# controller.net
KiCad netlist of a schematic drawn in EAGLE
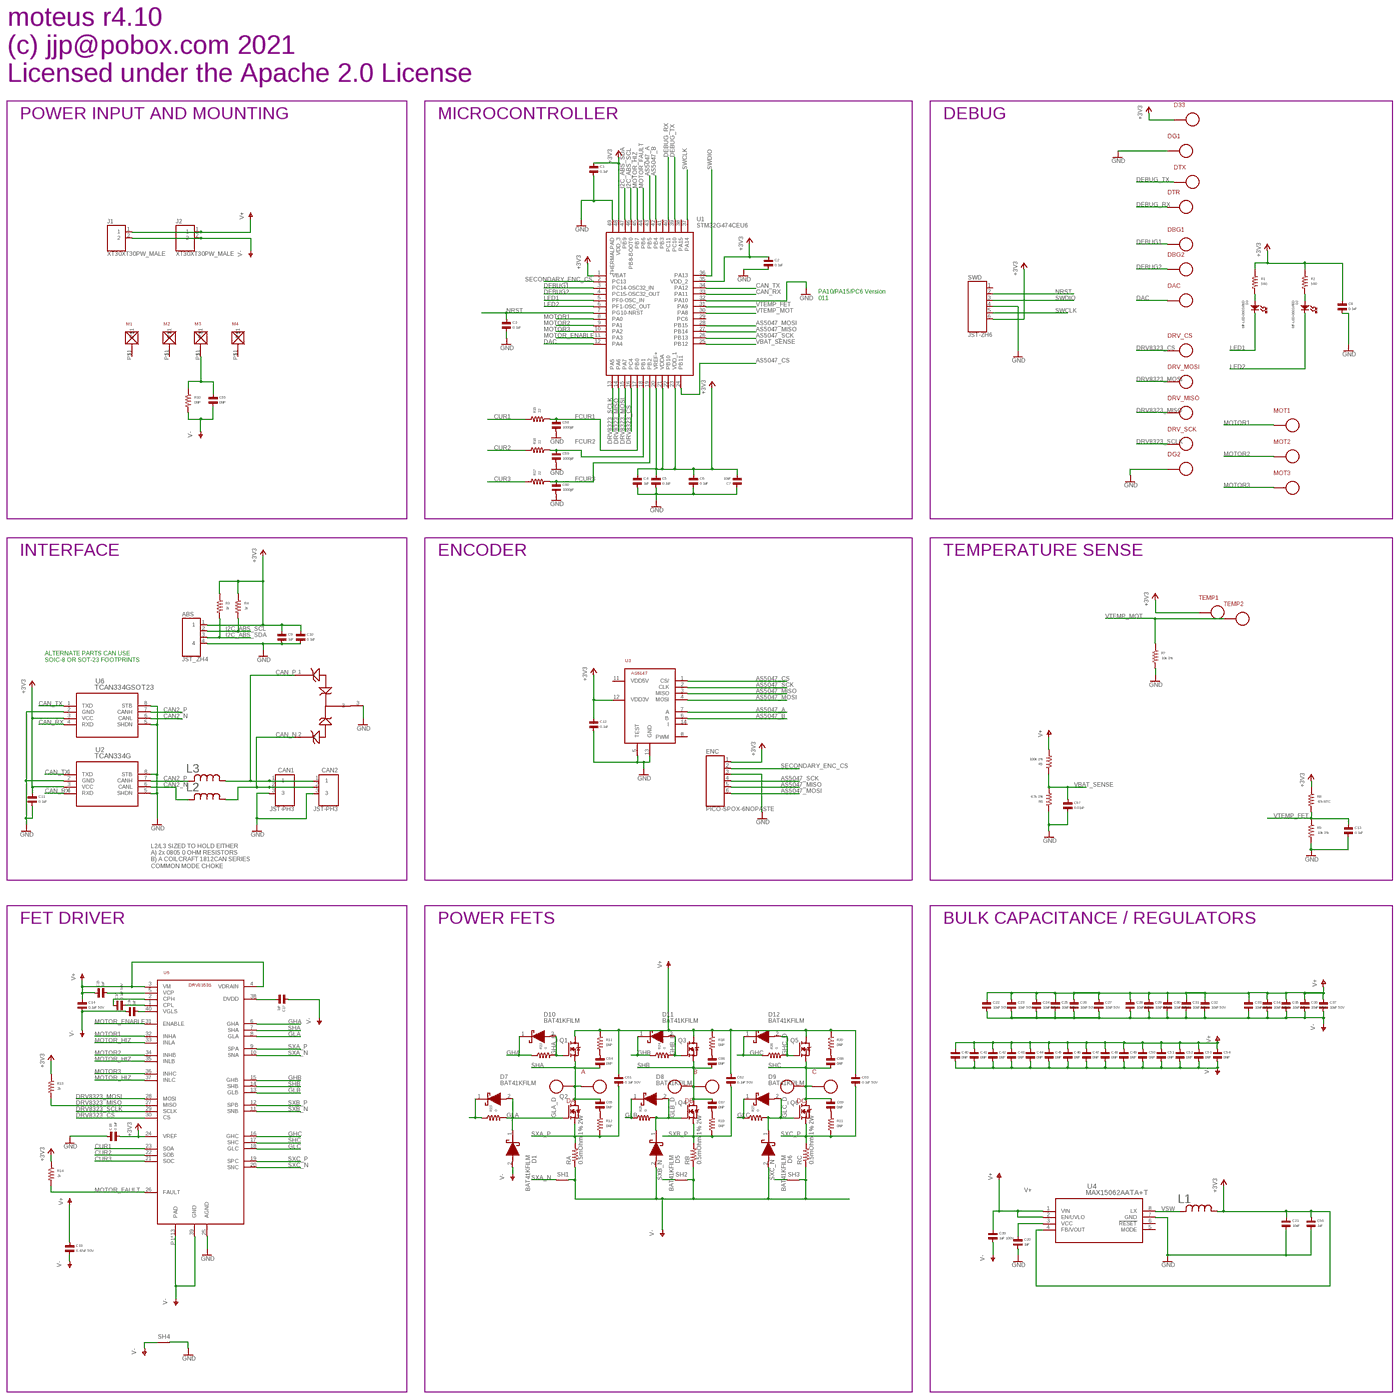
[diagram p0: schematic, sheet 1, overview]
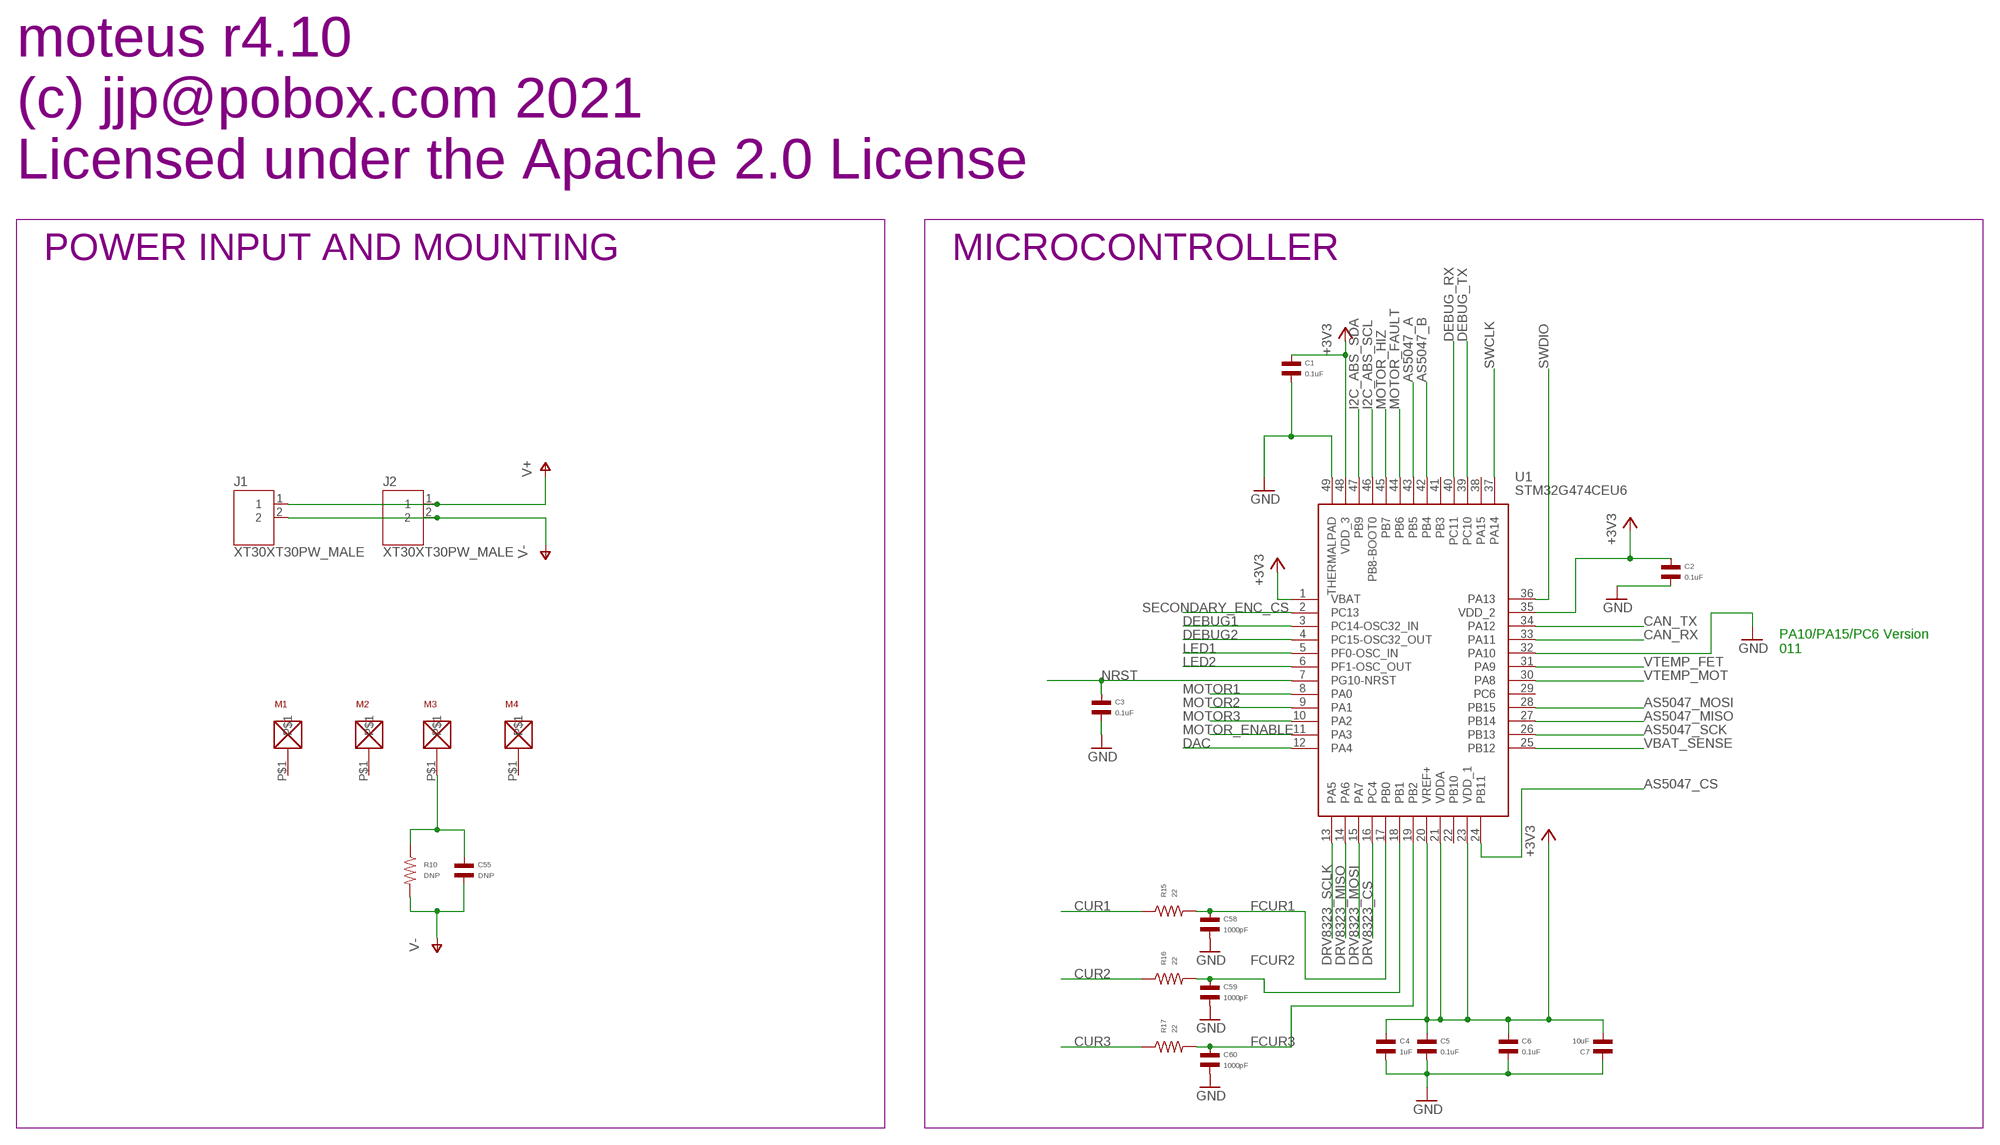
[diagram p1: schematic, sheet 1, part 1 of 4]
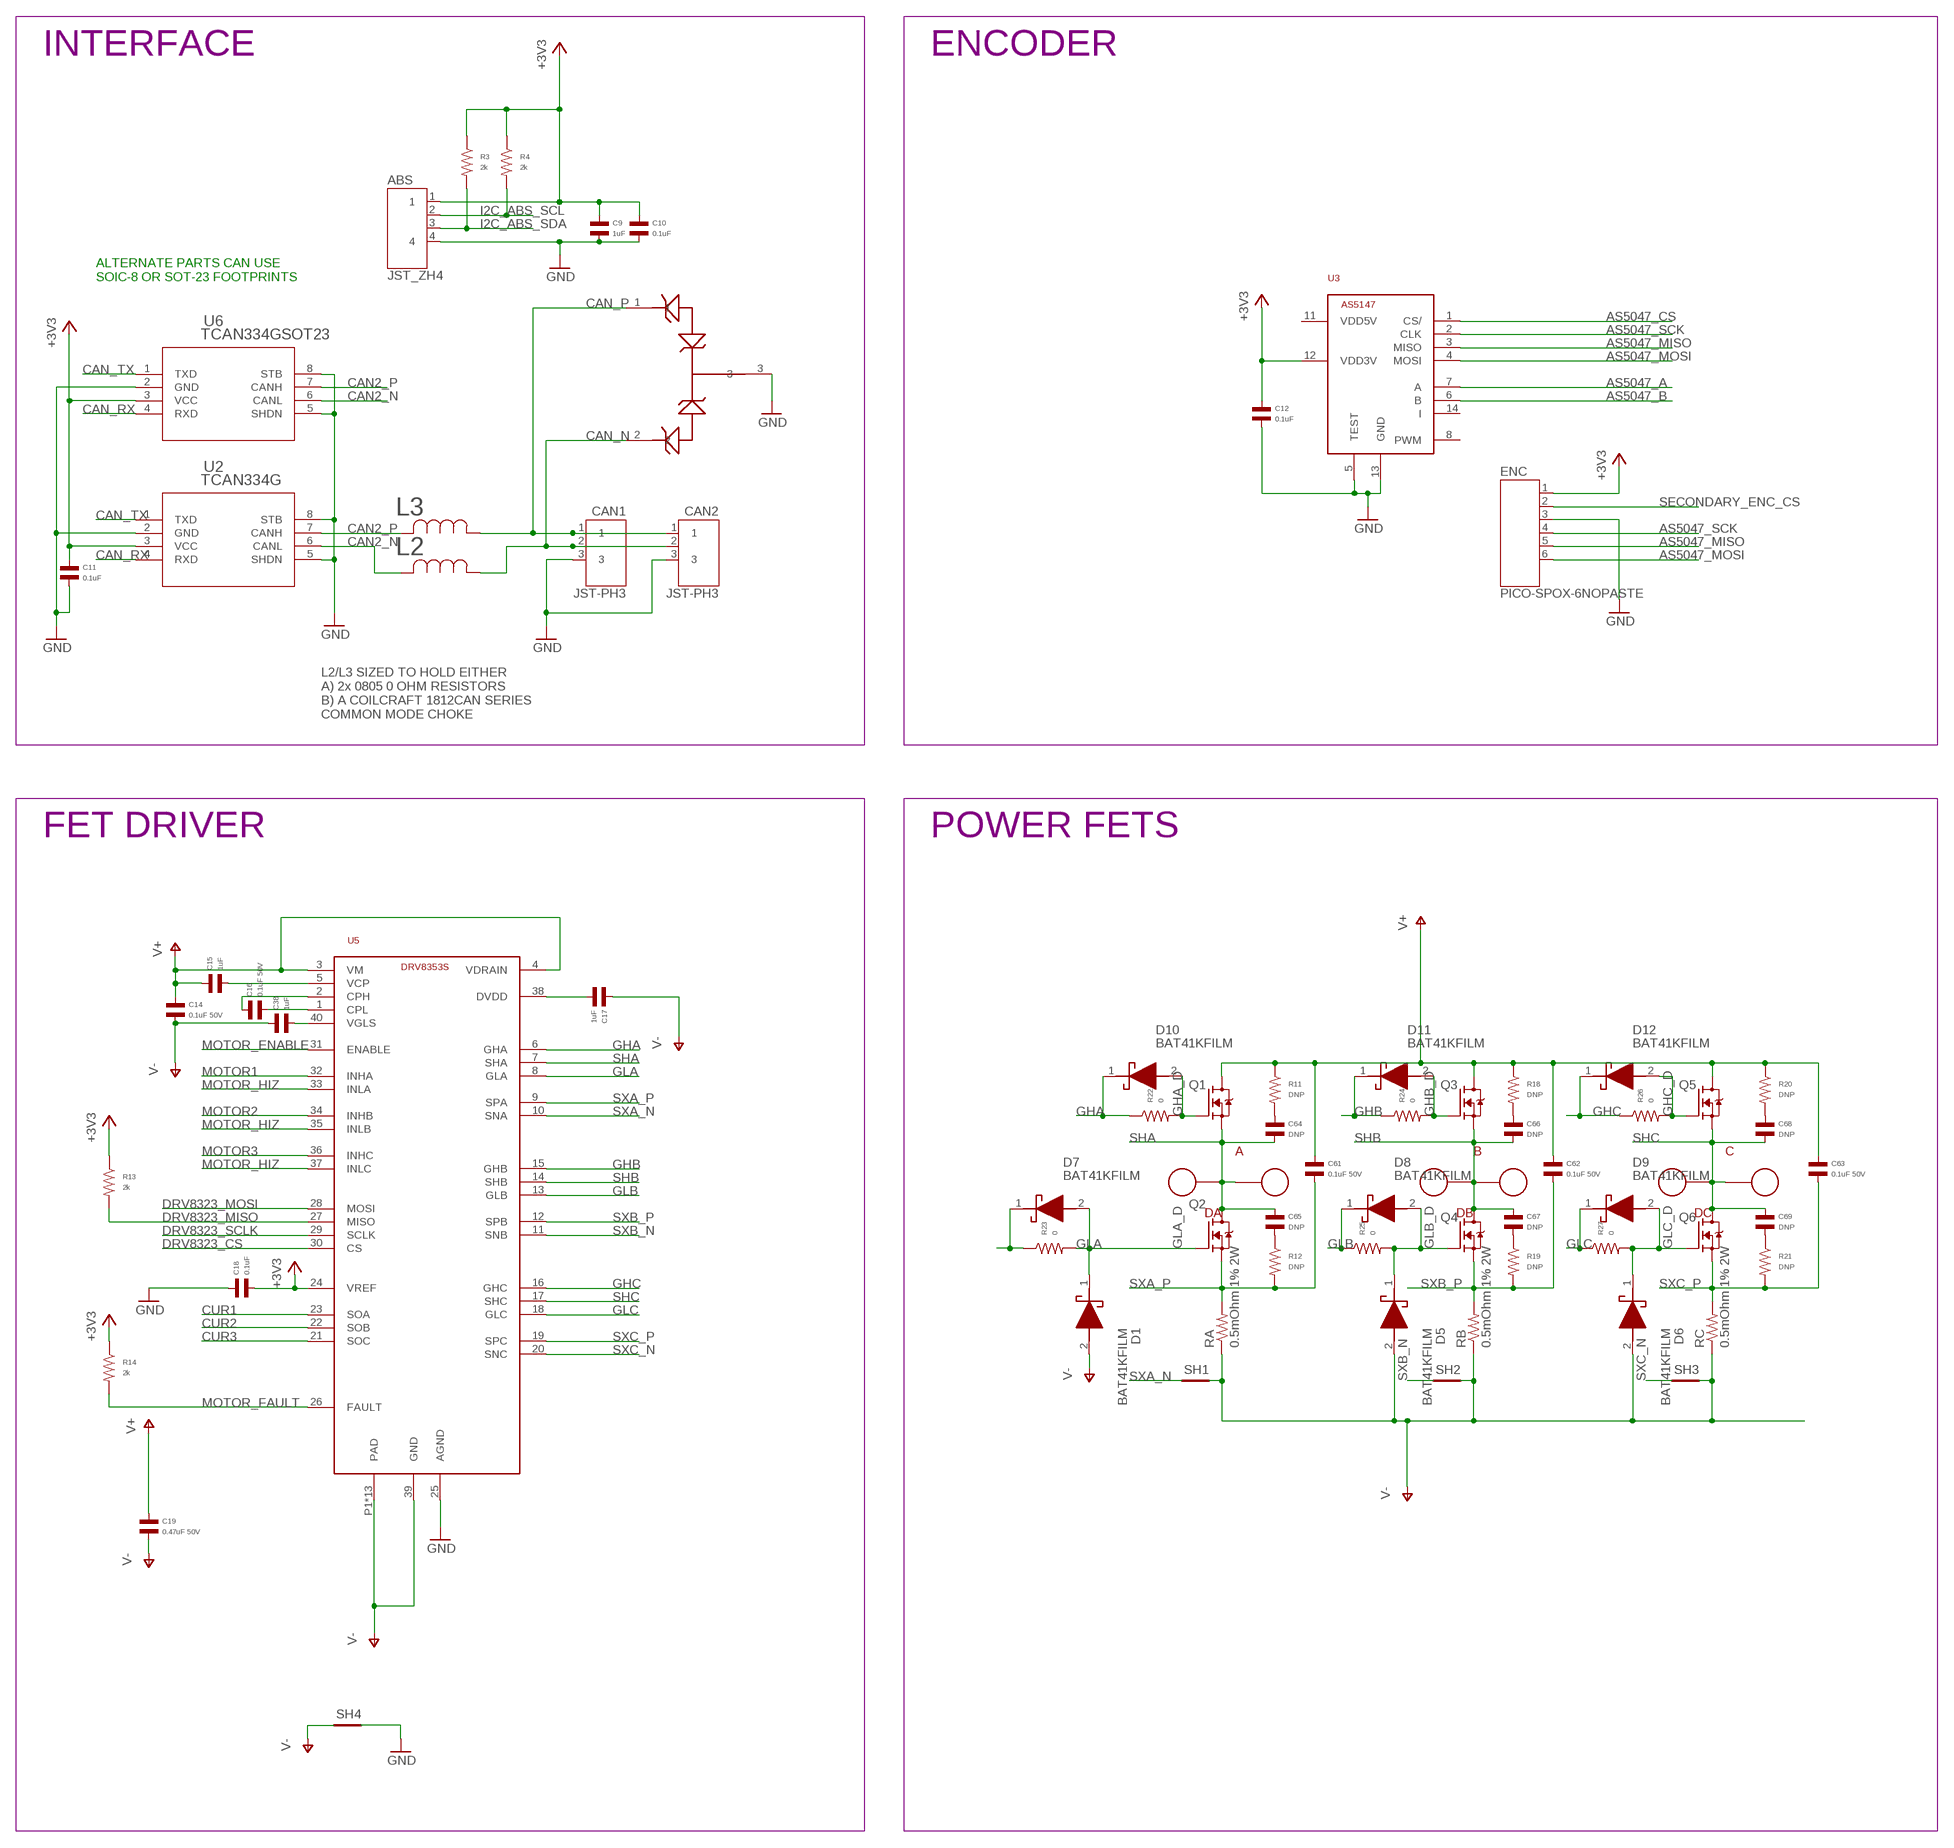
[diagram p2: schematic, sheet 1, part 2 of 4]
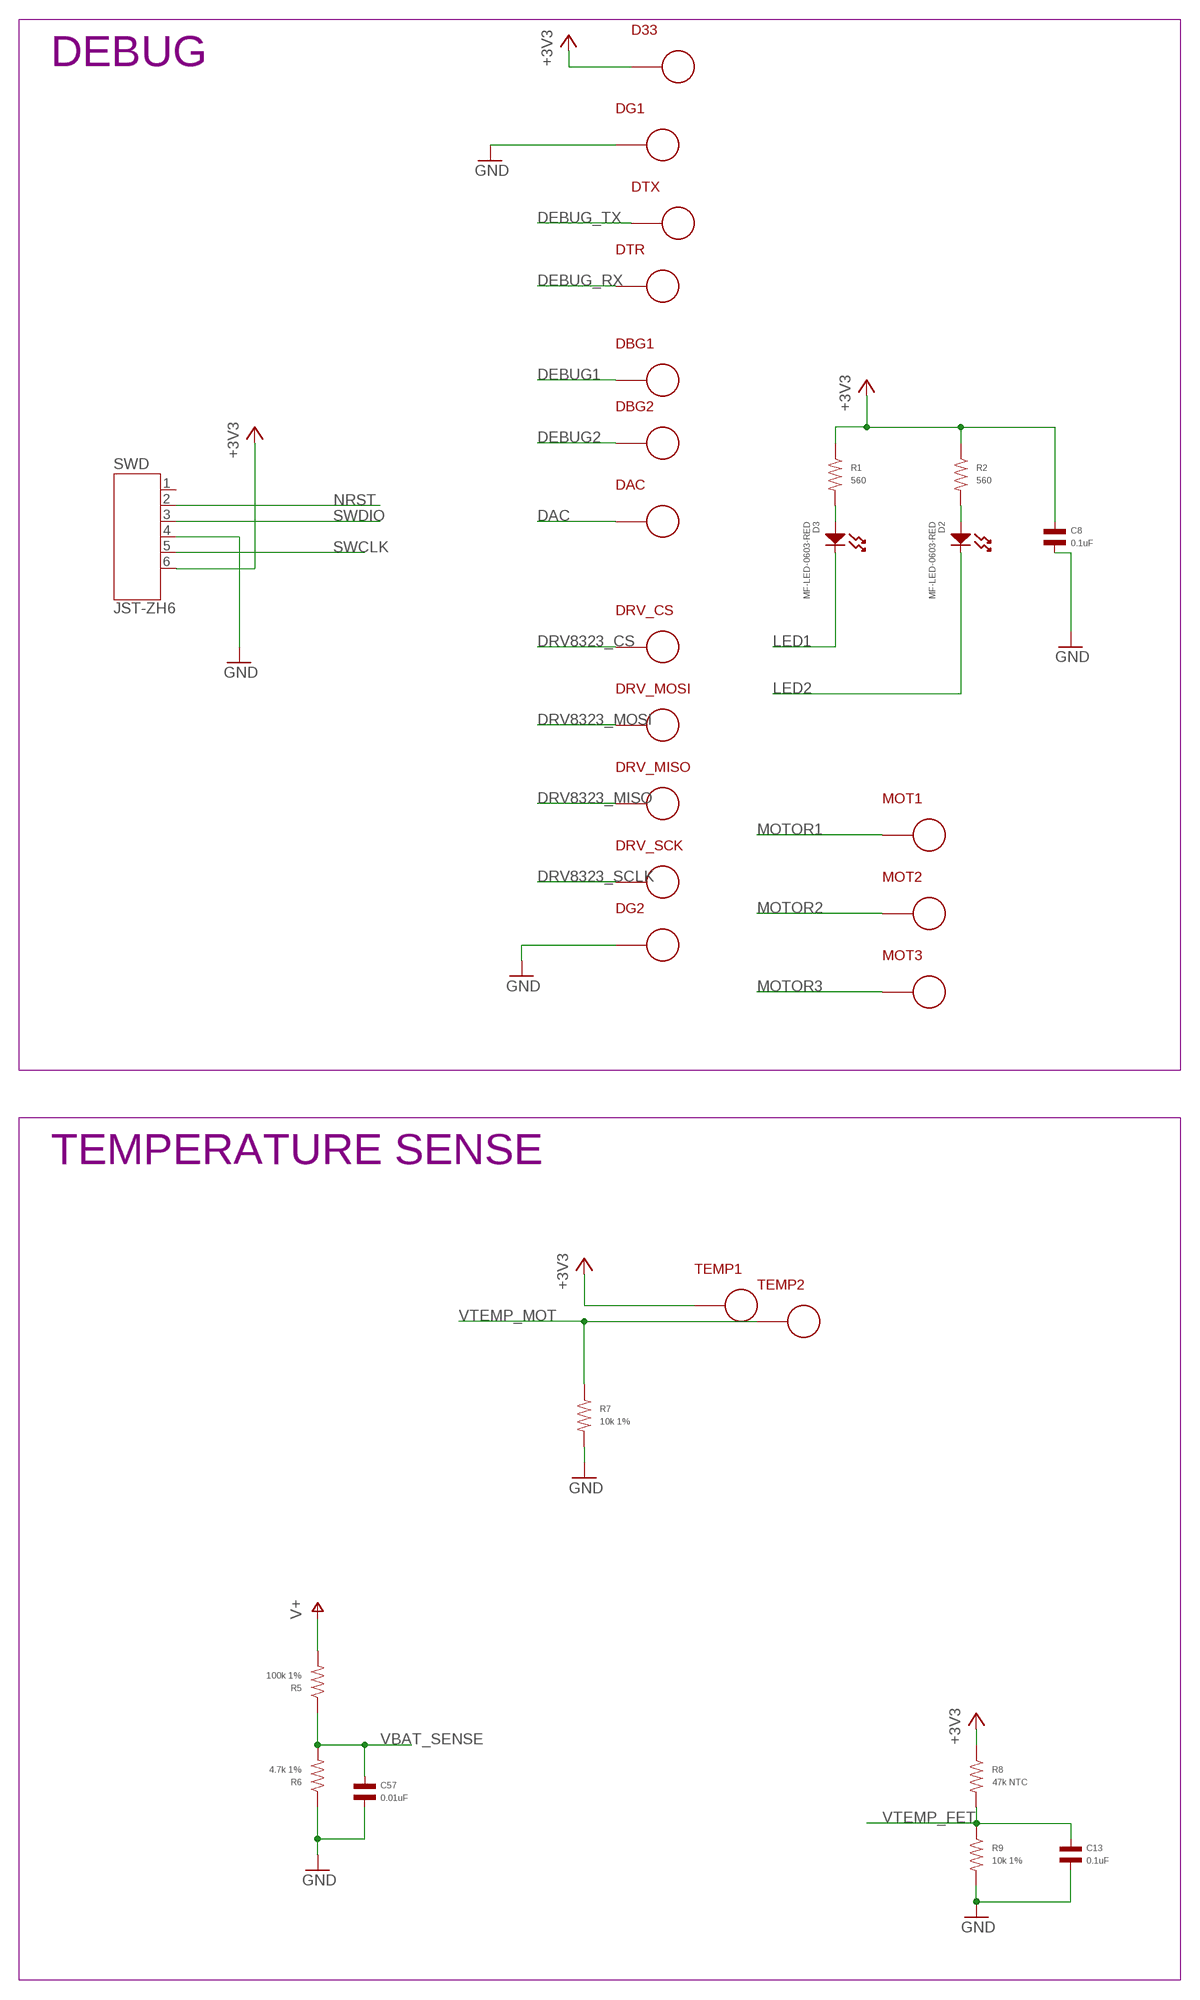
[diagram p3: schematic, sheet 1, part 3 of 4]
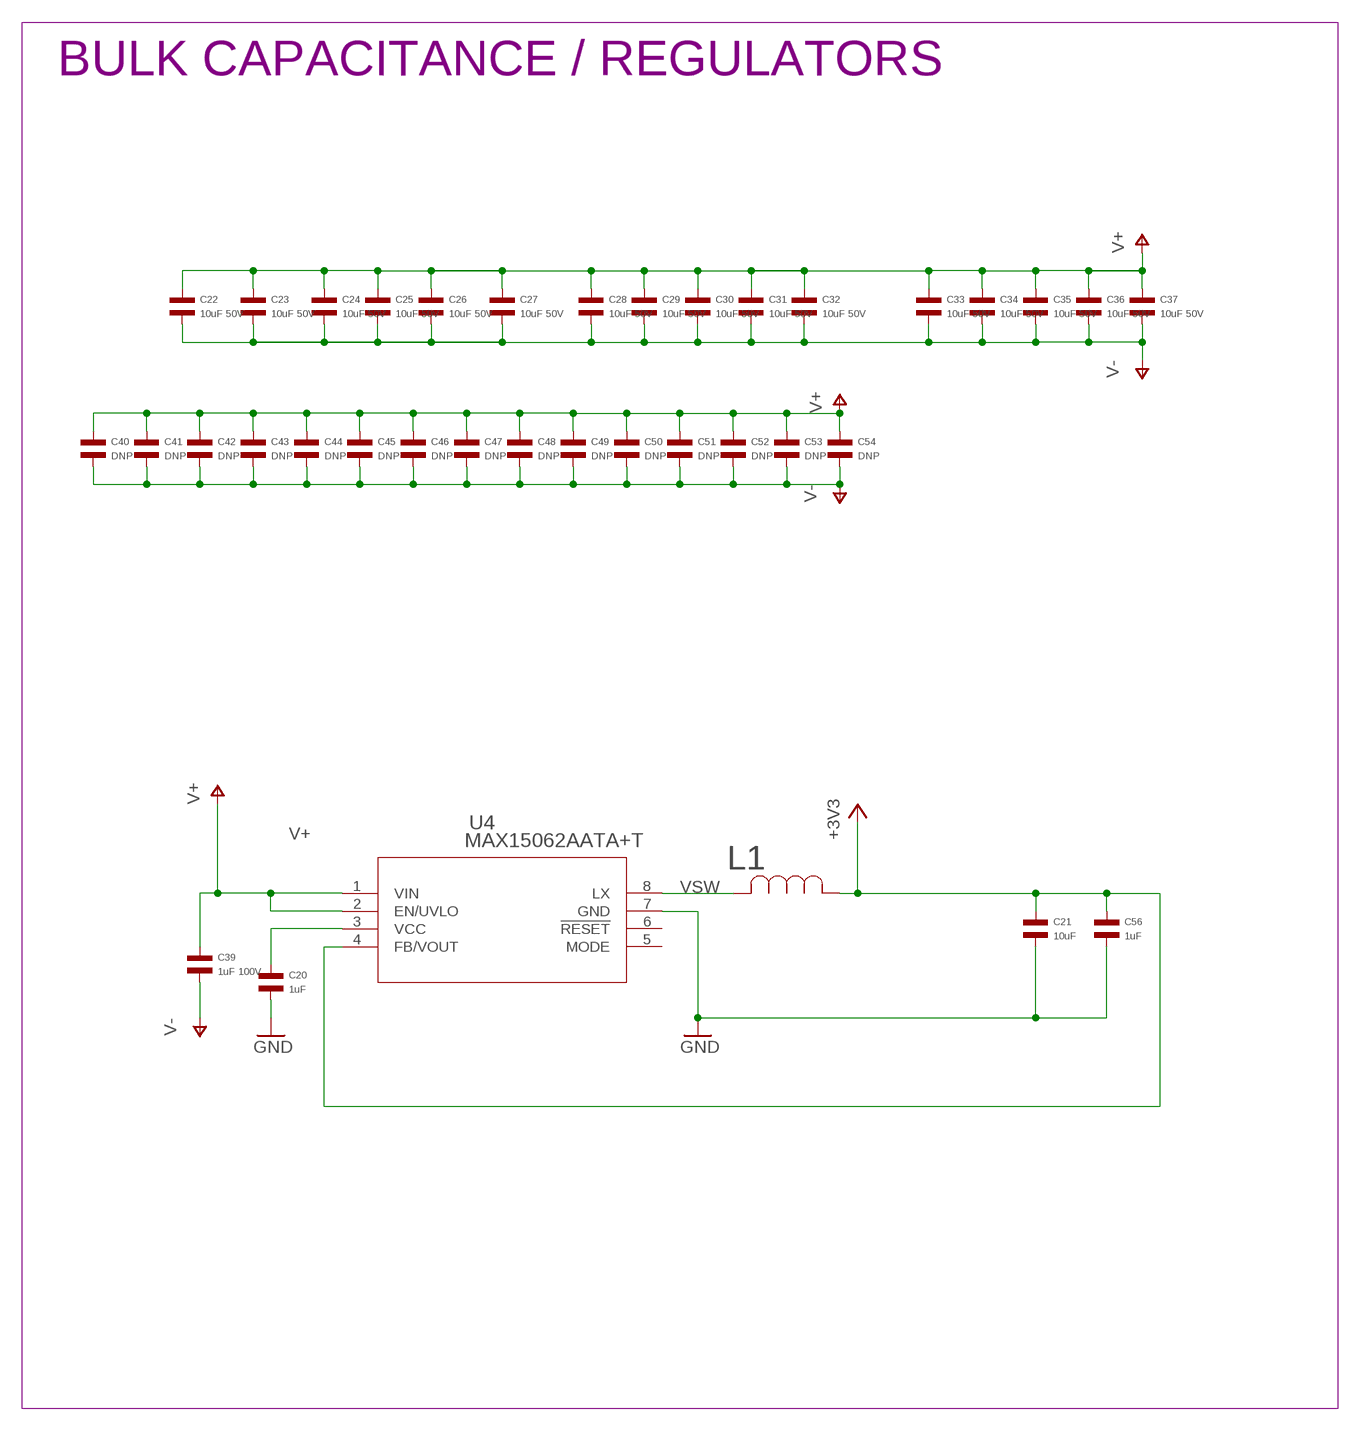
[diagram p4: schematic, sheet 1, part 4 of 4]

(export (version "E")
  (design (tool "Eeschema 10.0.6"))
  (components
    (comp (ref "A")
      (value "PAD16AWG_PAD")
      (footprint "eagle-import:16AWG_PAD")
      (libsource (lib "eagle-import") (part "PAD16AWG_PAD"))
    )
    (comp (ref "ABS")
      (value "JST_ZH4")
      (footprint "eagle-import:JST_S4B-ZR-SM4A-TF(LF)(SN)")
      (fields (field (name "MF") "JST") (field (name "MPN") "S4B-ZR-SM4A-TF(LF)(SN)"))
      (libsource (lib "eagle-import") (part "JST_ZH4"))
    )
    (comp (ref "B")
      (value "PAD16AWG_PAD")
      (footprint "eagle-import:16AWG_PAD")
      (libsource (lib "eagle-import") (part "PAD16AWG_PAD"))
    )
    (comp (ref "C")
      (value "PAD16AWG_PAD")
      (footprint "eagle-import:16AWG_PAD")
      (libsource (lib "eagle-import") (part "PAD16AWG_PAD"))
    )
    (comp (ref "C1")
      (value "0.1uF")
      (footprint "eagle-import:C0402")
      (fields (field (name "HOUSEPART") "YES") (field (name "MPN") "MF-CAP-0402-0.1uF"))
      (libsource (lib "eagle-import") (part "mfpassives_CAPACITOR_NP_0402"))
    )
    (comp (ref "C2")
      (value "0.1uF")
      (footprint "eagle-import:C0402")
      (fields (field (name "HOUSEPART") "YES") (field (name "MPN") "MF-CAP-0402-0.1uF"))
      (libsource (lib "eagle-import") (part "mfpassives_CAPACITOR_NP_0402"))
    )
    (comp (ref "C3")
      (value "0.1uF")
      (footprint "eagle-import:C0402")
      (fields (field (name "HOUSEPART") "YES") (field (name "MPN") "MF-CAP-0402-0.1uF"))
      (libsource (lib "eagle-import") (part "mfpassives_CAPACITOR_NP_0402"))
    )
    (comp (ref "C4")
      (value "1uF")
      (footprint "eagle-import:C0402")
      (fields (field (name "HOUSEPART") "YES") (field (name "MPN") "MF-CAP-0402-1uF"))
      (libsource (lib "eagle-import") (part "mfpassives_CAPACITOR_NP_0402"))
    )
    (comp (ref "C5")
      (value "0.1uF")
      (footprint "eagle-import:C0402")
      (fields (field (name "HOUSEPART") "YES") (field (name "MPN") "MF-CAP-0402-0.1uF"))
      (libsource (lib "eagle-import") (part "mfpassives_CAPACITOR_NP_0402"))
    )
    (comp (ref "C6")
      (value "0.1uF")
      (footprint "eagle-import:C0402")
      (fields (field (name "HOUSEPART") "YES") (field (name "MPN") "MF-CAP-0402-0.1uF"))
      (libsource (lib "eagle-import") (part "mfpassives_CAPACITOR_NP_0402"))
    )
    (comp (ref "C7")
      (value "10uF")
      (footprint "eagle-import:C1206")
      (fields (field (name "HOUSEPART") "YES") (field (name "MPN") "MF-CAP-1206-10uF"))
      (libsource (lib "eagle-import") (part "mfpassives_CAPACITOR_NP_1206"))
    )
    (comp (ref "C8")
      (value "0.1uF")
      (footprint "eagle-import:C0402")
      (fields (field (name "HOUSEPART") "YES") (field (name "MPN") "MF-CAP-0402-0.1uF"))
      (libsource (lib "eagle-import") (part "mfpassives_CAPACITOR_NP_0402"))
    )
    (comp (ref "C9")
      (value "1uF")
      (footprint "eagle-import:C0402")
      (fields (field (name "HOUSEPART") "YES") (field (name "MPN") "MF-CAP-0402-1uF"))
      (libsource (lib "eagle-import") (part "mfpassives_CAPACITOR_NP_0402"))
    )
    (comp (ref "C10")
      (value "0.1uF")
      (footprint "eagle-import:C0402")
      (fields (field (name "HOUSEPART") "YES") (field (name "MPN") "MF-CAP-0402-0.1uF"))
      (libsource (lib "eagle-import") (part "mfpassives_CAPACITOR_NP_0402"))
    )
    (comp (ref "C11")
      (value "0.1uF")
      (footprint "eagle-import:C0402_NOBORDER")
      (fields (field (name "HOUSEPART") "YES") (field (name "MPN") "MF-CAP-0402-0.1uF"))
      (libsource (lib "eagle-import") (part "CAPACITOR_NP_0402_NOBORDER"))
    )
    (comp (ref "C12")
      (value "0.1uF")
      (footprint "eagle-import:C0402")
      (fields (field (name "HOUSEPART") "YES") (field (name "MPN") "MF-CAP-0402-0.1uF"))
      (libsource (lib "eagle-import") (part "mfpassives_CAPACITOR_NP_0402"))
    )
    (comp (ref "C13")
      (value "0.1uF")
      (footprint "eagle-import:C0402")
      (fields (field (name "HOUSEPART") "YES") (field (name "MPN") "MF-CAP-0402-0.1uF"))
      (libsource (lib "eagle-import") (part "mfpassives_CAPACITOR_NP_0402"))
    )
    (comp (ref "C14")
      (value "0.1uF 50V")
      (footprint "eagle-import:C0402")
      (fields (field (name "MF") "TDK") (field (name "MPN") "CGA2B3X7R1H104K050BB"))
      (libsource (lib "eagle-import") (part "mfpassives_CAPACITOR_NP_0402"))
    )
    (comp (ref "C15")
      (value "1uF")
      (footprint "eagle-import:C0402")
      (fields (field (name "HOUSEPART") "YES") (field (name "MPN") "MF-CAP-0402-1uF"))
      (libsource (lib "eagle-import") (part "mfpassives_CAPACITOR_NP_0402"))
    )
    (comp (ref "C16")
      (value "0.1uF 50V")
      (footprint "eagle-import:C0402")
      (fields (field (name "MF") "TDK") (field (name "MPN") "CGA2B3X7R1H104K050BB"))
      (libsource (lib "eagle-import") (part "mfpassives_CAPACITOR_NP_0402"))
    )
    (comp (ref "C17")
      (value "1uF")
      (footprint "eagle-import:C0402")
      (fields (field (name "HOUSEPART") "YES") (field (name "MPN") "MF-CAP-0402-1uF"))
      (libsource (lib "eagle-import") (part "mfpassives_CAPACITOR_NP_0402"))
    )
    (comp (ref "C18")
      (value "0.1uF")
      (footprint "eagle-import:C0402")
      (fields (field (name "HOUSEPART") "YES") (field (name "MPN") "MF-CAP-0402-0.1uF"))
      (libsource (lib "eagle-import") (part "mfpassives_CAPACITOR_NP_0402"))
    )
    (comp (ref "C19")
      (value "0.47uF 50V")
      (footprint "eagle-import:C0402")
      (fields (field (name "MF") "Murata") (field (name "MPN") "GRM155R61H474KE11D"))
      (libsource (lib "eagle-import") (part "mfpassives_CAPACITOR_NP_0402"))
    )
    (comp (ref "C20")
      (value "1uF")
      (footprint "eagle-import:C0603")
      (fields (field (name "HOUSEPART") "1") (field (name "MPN") "MF-CAP-0603-1uF"))
      (libsource (lib "eagle-import") (part "mfpassives_CAPACITOR_NP_0603"))
    )
    (comp (ref "C21")
      (value "10uF")
      (footprint "eagle-import:C1206")
      (fields (field (name "HOUSEPART") "1") (field (name "MPN") "MF-CAP-1206-10uF"))
      (libsource (lib "eagle-import") (part "mfpassives_CAPACITOR_NP_1206"))
    )
    (comp (ref "C22")
      (value "10uF 50V")
      (footprint "eagle-import:C1206")
      (fields (field (name "MF") "TDK") (field (name "MPN") "C3216X7R1H106K160AE"))
      (libsource (lib "eagle-import") (part "mfpassives_CAPACITOR_NP_1206"))
    )
    (comp (ref "C23")
      (value "10uF 50V")
      (footprint "eagle-import:C1206")
      (fields (field (name "MF") "TDK") (field (name "MPN") "C3216X7R1H106K160AE"))
      (libsource (lib "eagle-import") (part "mfpassives_CAPACITOR_NP_1206"))
    )
    (comp (ref "C24")
      (value "10uF 50V")
      (footprint "eagle-import:C1206")
      (fields (field (name "MF") "TDK") (field (name "MPN") "C3216X7R1H106K160AE"))
      (libsource (lib "eagle-import") (part "mfpassives_CAPACITOR_NP_1206"))
    )
    (comp (ref "C25")
      (value "10uF 50V")
      (footprint "eagle-import:C1206")
      (fields (field (name "MF") "TDK") (field (name "MPN") "C3216X7R1H106K160AE"))
      (libsource (lib "eagle-import") (part "mfpassives_CAPACITOR_NP_1206"))
    )
    (comp (ref "C26")
      (value "10uF 50V")
      (footprint "eagle-import:C1206")
      (fields (field (name "MF") "TDK") (field (name "MPN") "C3216X7R1H106K160AE"))
      (libsource (lib "eagle-import") (part "mfpassives_CAPACITOR_NP_1206"))
    )
    (comp (ref "C27")
      (value "10uF 50V")
      (footprint "eagle-import:C1206")
      (fields (field (name "MF") "TDK") (field (name "MPN") "C3216X7R1H106K160AE"))
      (libsource (lib "eagle-import") (part "mfpassives_CAPACITOR_NP_1206"))
    )
    (comp (ref "C28")
      (value "10uF 50V")
      (footprint "eagle-import:C1206")
      (fields (field (name "MF") "TDK") (field (name "MPN") "C3216X7R1H106K160AE"))
      (libsource (lib "eagle-import") (part "mfpassives_CAPACITOR_NP_1206"))
    )
    (comp (ref "C29")
      (value "10uF 50V")
      (footprint "eagle-import:C1206")
      (fields (field (name "MF") "TDK") (field (name "MPN") "C3216X7R1H106K160AE"))
      (libsource (lib "eagle-import") (part "mfpassives_CAPACITOR_NP_1206"))
    )
    (comp (ref "C30")
      (value "10uF 50V")
      (footprint "eagle-import:C1206")
      (fields (field (name "MF") "TDK") (field (name "MPN") "C3216X7R1H106K160AE"))
      (libsource (lib "eagle-import") (part "mfpassives_CAPACITOR_NP_1206"))
    )
    (comp (ref "C31")
      (value "10uF 50V")
      (footprint "eagle-import:C1206")
      (fields (field (name "MF") "TDK") (field (name "MPN") "C3216X7R1H106K160AE"))
      (libsource (lib "eagle-import") (part "mfpassives_CAPACITOR_NP_1206"))
    )
    (comp (ref "C32")
      (value "10uF 50V")
      (footprint "eagle-import:C1206")
      (fields (field (name "MF") "TDK") (field (name "MPN") "C3216X7R1H106K160AE"))
      (libsource (lib "eagle-import") (part "mfpassives_CAPACITOR_NP_1206"))
    )
    (comp (ref "C33")
      (value "10uF 50V")
      (footprint "eagle-import:C1206")
      (fields (field (name "MF") "TDK") (field (name "MPN") "C3216X7R1H106K160AE"))
      (libsource (lib "eagle-import") (part "mfpassives_CAPACITOR_NP_1206"))
    )
    (comp (ref "C34")
      (value "10uF 50V")
      (footprint "eagle-import:C1206")
      (fields (field (name "MF") "TDK") (field (name "MPN") "C3216X7R1H106K160AE"))
      (libsource (lib "eagle-import") (part "mfpassives_CAPACITOR_NP_1206"))
    )
    (comp (ref "C35")
      (value "10uF 50V")
      (footprint "eagle-import:C1206_NOBORDER")
      (fields (field (name "MF") "TDK") (field (name "MPN") "C3216X7R1H106K160AE"))
      (libsource (lib "eagle-import") (part "CAPACITOR_NP_1206_NOBORDER"))
    )
    (comp (ref "C36")
      (value "10uF 50V")
      (footprint "eagle-import:C1206")
      (fields (field (name "MF") "TDK") (field (name "MPN") "C3216X7R1H106K160AE"))
      (libsource (lib "eagle-import") (part "mfpassives_CAPACITOR_NP_1206"))
    )
    (comp (ref "C37")
      (value "10uF 50V")
      (footprint "eagle-import:C1206")
      (fields (field (name "MF") "TDK") (field (name "MPN") "C3216X7R1H106K160AE"))
      (libsource (lib "eagle-import") (part "mfpassives_CAPACITOR_NP_1206"))
    )
    (comp (ref "C38")
      (value "1uF")
      (footprint "eagle-import:C0603")
      (fields
        (field (name "HOUSEPART") "YES")
        (field (name "MF") "TDK")
        (field (name "MPN") "C1608X7R1E105K080AE")
      )
      (libsource (lib "eagle-import") (part "mfpassives_CAPACITOR_NP_0603"))
    )
    (comp (ref "C39")
      (value "1uF 100V")
      (footprint "eagle-import:C0805")
      (fields (field (name "MF") "MURATA") (field (name "MPN") "GCM21BC72A105KE36L"))
      (libsource (lib "eagle-import") (part "mfpassives_CAPACITOR_NP_0805"))
    )
    (comp (ref "C40")
      (value "DNP")
      (footprint "eagle-import:C1206_NOCREAM")
      (libsource (lib "eagle-import") (part "CAPACITOR_NP_1206_NOCREAM"))
    )
    (comp (ref "C41")
      (value "DNP")
      (footprint "eagle-import:C1206_NOCREAM")
      (libsource (lib "eagle-import") (part "CAPACITOR_NP_1206_NOCREAM"))
    )
    (comp (ref "C42")
      (value "DNP")
      (footprint "eagle-import:C1206_NOCREAM")
      (libsource (lib "eagle-import") (part "CAPACITOR_NP_1206_NOCREAM"))
    )
    (comp (ref "C43")
      (value "DNP")
      (footprint "eagle-import:C1206_NOCREAM")
      (libsource (lib "eagle-import") (part "CAPACITOR_NP_1206_NOCREAM"))
    )
    (comp (ref "C44")
      (value "DNP")
      (footprint "eagle-import:C1206_NOCREAM")
      (libsource (lib "eagle-import") (part "CAPACITOR_NP_1206_NOCREAM"))
    )
    (comp (ref "C45")
      (value "DNP")
      (footprint "eagle-import:C1206_NOCREAM")
      (libsource (lib "eagle-import") (part "CAPACITOR_NP_1206_NOCREAM"))
    )
    (comp (ref "C46")
      (value "DNP")
      (footprint "eagle-import:C1206_NOCREAM")
      (libsource (lib "eagle-import") (part "CAPACITOR_NP_1206_NOCREAM"))
    )
    (comp (ref "C47")
      (value "DNP")
      (footprint "eagle-import:C1206_NOCREAM")
      (libsource (lib "eagle-import") (part "CAPACITOR_NP_1206_NOCREAM"))
    )
    (comp (ref "C48")
      (value "DNP")
      (footprint "eagle-import:C1206_NOCREAM")
      (libsource (lib "eagle-import") (part "CAPACITOR_NP_1206_NOCREAM"))
    )
    (comp (ref "C49")
      (value "DNP")
      (footprint "eagle-import:C1206_NOCREAM")
      (libsource (lib "eagle-import") (part "CAPACITOR_NP_1206_NOCREAM"))
    )
    (comp (ref "C50")
      (value "DNP")
      (footprint "eagle-import:C1206_NOCREAM")
      (libsource (lib "eagle-import") (part "CAPACITOR_NP_1206_NOCREAM"))
    )
    (comp (ref "C51")
      (value "DNP")
      (footprint "eagle-import:C1206_NOCREAM")
      (libsource (lib "eagle-import") (part "CAPACITOR_NP_1206_NOCREAM"))
    )
    (comp (ref "C52")
      (value "DNP")
      (footprint "eagle-import:C1206_NOCREAM")
      (libsource (lib "eagle-import") (part "CAPACITOR_NP_1206_NOCREAM"))
    )
    (comp (ref "C53")
      (value "DNP")
      (footprint "eagle-import:C1206_NOCREAM")
      (libsource (lib "eagle-import") (part "CAPACITOR_NP_1206_NOCREAM"))
    )
    (comp (ref "C54")
      (value "DNP")
      (footprint "eagle-import:C1206_NOCREAM")
      (libsource (lib "eagle-import") (part "CAPACITOR_NP_1206_NOCREAM"))
    )
    (comp (ref "C55")
      (value "DNP")
      (footprint "eagle-import:C0402")
      (fields (field (name "POPULATE") "0"))
      (libsource (lib "eagle-import") (part "mfpassives_CAPACITOR_NP_0402"))
    )
    (comp (ref "C56")
      (value "1uF")
      (footprint "eagle-import:C0402")
      (fields (field (name "HOUSEPART") "YES") (field (name "MPN") "MF-CAP-0402-1uF"))
      (libsource (lib "eagle-import") (part "mfpassives_CAPACITOR_NP_0402"))
    )
    (comp (ref "C57")
      (value "0.01uF")
      (footprint "eagle-import:C0402")
      (fields (field (name "HOUSEPART") "YES") (field (name "MPN") "MF-CAP-0402-0.01uF"))
      (libsource (lib "eagle-import") (part "mfpassives_CAPACITOR_NP_0402"))
    )
    (comp (ref "C58")
      (value "1000pF")
      (footprint "eagle-import:C0402_NOBORDER")
      (fields (field (name "HOUSEPART") "1") (field (name "MPN") "MF-CAP-0402-1nF"))
      (libsource (lib "eagle-import") (part "CAPACITOR_NP_0402_NOBORDER"))
    )
    (comp (ref "C59")
      (value "1000pF")
      (footprint "eagle-import:C0402_NOBORDER")
      (fields (field (name "HOUSEPART") "1") (field (name "MPN") "MF-CAP-0402-1nF"))
      (libsource (lib "eagle-import") (part "CAPACITOR_NP_0402_NOBORDER"))
    )
    (comp (ref "C60")
      (value "1000pF")
      (footprint "eagle-import:C0402_NOBORDER")
      (fields (field (name "HOUSEPART") "1") (field (name "MPN") "MF-CAP-0402-1nF"))
      (libsource (lib "eagle-import") (part "CAPACITOR_NP_0402_NOBORDER"))
    )
    (comp (ref "C61")
      (value "0.1uF 50V")
      (footprint "eagle-import:C1206")
      (fields (field (name "MF") "KYOCERA AVX") (field (name "MPN") "12065C104KAZ2A"))
      (libsource (lib "eagle-import") (part "mfpassives_CAPACITOR_NP_1206"))
    )
    (comp (ref "C62")
      (value "0.1uF 50V")
      (footprint "eagle-import:C0603_NOBORDER")
      (fields (field (name "MF") "KYOCERA AVX") (field (name "MPN") "06035C104KAZ2A"))
      (libsource (lib "eagle-import") (part "CAPACITOR_NP_0603_NOBORDER"))
    )
    (comp (ref "C63")
      (value "0.1uF 50V")
      (footprint "eagle-import:C1206")
      (fields (field (name "MF") "KYOCERA AVX") (field (name "MPN") "12065C104KAZ2A"))
      (libsource (lib "eagle-import") (part "mfpassives_CAPACITOR_NP_1206"))
    )
    (comp (ref "C64")
      (value "DNP")
      (footprint "eagle-import:C0603")
      (fields (field (name "POPULATE") "0"))
      (libsource (lib "eagle-import") (part "mfpassives_CAPACITOR_NP_0603"))
    )
    (comp (ref "C65")
      (value "DNP")
      (footprint "eagle-import:C0603")
      (fields (field (name "POPULATE") "0"))
      (libsource (lib "eagle-import") (part "mfpassives_CAPACITOR_NP_0603"))
    )
    (comp (ref "C66")
      (value "DNP")
      (footprint "eagle-import:C0603")
      (fields (field (name "POPULATE") "0"))
      (libsource (lib "eagle-import") (part "mfpassives_CAPACITOR_NP_0603"))
    )
    (comp (ref "C67")
      (value "DNP")
      (footprint "eagle-import:C0603")
      (fields (field (name "POPULATE") "0"))
      (libsource (lib "eagle-import") (part "mfpassives_CAPACITOR_NP_0603"))
    )
    (comp (ref "C68")
      (value "DNP")
      (footprint "eagle-import:C0603")
      (fields (field (name "POPULATE") "0"))
      (libsource (lib "eagle-import") (part "mfpassives_CAPACITOR_NP_0603"))
    )
    (comp (ref "C69")
      (value "DNP")
      (footprint "eagle-import:C0603")
      (fields (field (name "POPULATE") "0"))
      (libsource (lib "eagle-import") (part "mfpassives_CAPACITOR_NP_0603"))
    )
    (comp (ref "CAN1")
      (value "JST-PH3")
      (footprint "eagle-import:JST_S3B-PH-SM4-TB(LF)(SN)")
      (fields (field (name "MF") "JST") (field (name "MPN") "S3B-PH-SM4-TB(LF)(SN)"))
      (libsource (lib "eagle-import") (part "JST-PH3"))
    )
    (comp (ref "CAN2")
      (value "JST-PH3")
      (footprint "eagle-import:JST_S3B-PH-SM4-TB(LF)(SN)")
      (fields (field (name "MF") "JST") (field (name "MPN") "S3B-PH-SM4-TB(LF)(SN)"))
      (libsource (lib "eagle-import") (part "JST-PH3"))
    )
    (comp (ref "D1")
      (value "BAT41KFILM")
      (footprint "eagle-import:SODFL1608X70N")
      (fields (field (name "MOUSER_PART_NUMBER") "511-BAT41KFILM") (field (name "MF") "ST"))
      (libsource (lib "eagle-import") (part "BAT41KFILM"))
    )
    (comp (ref "D2")
      (value "MF-LED-0603-RED")
      (footprint "eagle-import:LED0603")
      (fields (field (name "HOUSEPART") "YES") (field (name "MPN") "MF-LED-0603-GREEN"))
      (libsource (lib "eagle-import") (part "LED_SINGLE-0603-RED"))
    )
    (comp (ref "D3")
      (value "MF-LED-0603-RED")
      (footprint "eagle-import:LED0603")
      (fields (field (name "HOUSEPART") "YES"))
      (libsource (lib "eagle-import") (part "LED_SINGLE-0603-RED"))
    )
    (comp (ref "D4")
      (value "DUAL_TVS")
      (footprint "eagle-import:SOT23-3")
      (fields (field (name "MPN") "CDSOT23-0502B"))
      (libsource (lib "eagle-import") (part "DUAL_TVS"))
    )
    (comp (ref "D5")
      (value "BAT41KFILM")
      (footprint "eagle-import:SODFL1608X70N")
      (fields (field (name "MOUSER_PART_NUMBER") "511-BAT41KFILM") (field (name "MF") "ST"))
      (libsource (lib "eagle-import") (part "BAT41KFILM"))
    )
    (comp (ref "D6")
      (value "BAT41KFILM")
      (footprint "eagle-import:SODFL1608X70N")
      (fields (field (name "MOUSER_PART_NUMBER") "511-BAT41KFILM") (field (name "MF") "ST"))
      (libsource (lib "eagle-import") (part "BAT41KFILM"))
    )
    (comp (ref "D7")
      (value "BAT41KFILM")
      (footprint "eagle-import:SODFL1608X70N")
      (fields (field (name "MOUSER_PART_NUMBER") "511-BAT41KFILM") (field (name "MF") "ST"))
      (libsource (lib "eagle-import") (part "BAT41KFILM"))
    )
    (comp (ref "D8")
      (value "BAT41KFILM")
      (footprint "eagle-import:SODFL1608X70N")
      (fields (field (name "MOUSER_PART_NUMBER") "511-BAT41KFILM") (field (name "MF") "ST"))
      (libsource (lib "eagle-import") (part "BAT41KFILM"))
    )
    (comp (ref "D9")
      (value "BAT41KFILM")
      (footprint "eagle-import:SODFL1608X70N")
      (fields (field (name "MOUSER_PART_NUMBER") "511-BAT41KFILM") (field (name "MF") "ST"))
      (libsource (lib "eagle-import") (part "BAT41KFILM"))
    )
    (comp (ref "D10")
      (value "BAT41KFILM")
      (footprint "eagle-import:SODFL1608X70N")
      (fields (field (name "MOUSER_PART_NUMBER") "511-BAT41KFILM") (field (name "MF") "ST"))
      (libsource (lib "eagle-import") (part "BAT41KFILM"))
    )
    (comp (ref "D11")
      (value "BAT41KFILM")
      (footprint "eagle-import:SODFL1608X70N")
      (fields (field (name "MOUSER_PART_NUMBER") "511-BAT41KFILM") (field (name "MF") "ST"))
      (libsource (lib "eagle-import") (part "BAT41KFILM"))
    )
    (comp (ref "D12")
      (value "BAT41KFILM")
      (footprint "eagle-import:SODFL1608X70N")
      (fields (field (name "MOUSER_PART_NUMBER") "511-BAT41KFILM") (field (name "MF") "ST"))
      (libsource (lib "eagle-import") (part "BAT41KFILM"))
    )
    (comp (ref "D33")
      (value "PAD24AWG_PAD")
      (footprint "eagle-import:24AWG_PAD")
      (libsource (lib "eagle-import") (part "PAD24AWG_PAD"))
    )
    (comp (ref "DA")
      (value "PAD24AWG_PAD")
      (footprint "eagle-import:24AWG_PAD")
      (libsource (lib "eagle-import") (part "PAD24AWG_PAD"))
    )
    (comp (ref "DAC")
      (value "PAD24AWG_PAD")
      (footprint "eagle-import:24AWG_PAD")
      (libsource (lib "eagle-import") (part "PAD24AWG_PAD"))
    )
    (comp (ref "DB")
      (value "PAD24AWG_PAD")
      (footprint "eagle-import:24AWG_PAD")
      (libsource (lib "eagle-import") (part "PAD24AWG_PAD"))
    )
    (comp (ref "DBG1")
      (value "PAD24AWG_PAD")
      (footprint "eagle-import:24AWG_PAD")
      (libsource (lib "eagle-import") (part "PAD24AWG_PAD"))
    )
    (comp (ref "DBG2")
      (value "PAD24AWG_PAD")
      (footprint "eagle-import:24AWG_PAD")
      (libsource (lib "eagle-import") (part "PAD24AWG_PAD"))
    )
    (comp (ref "DC")
      (value "PAD24AWG_PAD")
      (footprint "eagle-import:24AWG_PAD")
      (libsource (lib "eagle-import") (part "PAD24AWG_PAD"))
    )
    (comp (ref "DG1")
      (value "PAD24AWG_PAD")
      (footprint "eagle-import:24AWG_PAD")
      (libsource (lib "eagle-import") (part "PAD24AWG_PAD"))
    )
    (comp (ref "DG2")
      (value "PAD24AWG_PAD")
      (footprint "eagle-import:24AWG_PAD")
      (libsource (lib "eagle-import") (part "PAD24AWG_PAD"))
    )
    (comp (ref "DRV_CS")
      (value "PAD24AWG_PAD")
      (footprint "eagle-import:24AWG_PAD")
      (libsource (lib "eagle-import") (part "PAD24AWG_PAD"))
    )
    (comp (ref "DRV_MISO")
      (value "PAD24AWG_PAD")
      (footprint "eagle-import:24AWG_PAD")
      (libsource (lib "eagle-import") (part "PAD24AWG_PAD"))
    )
    (comp (ref "DRV_MOSI")
      (value "PAD24AWG_PAD")
      (footprint "eagle-import:24AWG_PAD")
      (libsource (lib "eagle-import") (part "PAD24AWG_PAD"))
    )
    (comp (ref "DRV_SCK")
      (value "PAD24AWG_PAD")
      (footprint "eagle-import:24AWG_PAD")
      (libsource (lib "eagle-import") (part "PAD24AWG_PAD"))
    )
    (comp (ref "DTR")
      (value "PAD24AWG_PAD")
      (footprint "eagle-import:24AWG_PAD")
      (libsource (lib "eagle-import") (part "PAD24AWG_PAD"))
    )
    (comp (ref "DTX")
      (value "PAD24AWG_PAD")
      (footprint "eagle-import:24AWG_PAD")
      (libsource (lib "eagle-import") (part "PAD24AWG_PAD"))
    )
    (comp (ref "ENC")
      (value "PICO-SPOX-6NOPASTE")
      (footprint "eagle-import:PICO-SPOX-SMT-RA-6-NOPASTE")
      (libsource (lib "eagle-import") (part "PICO-SPOX-6NOPASTE"))
    )
    (comp (ref "J1")
      (value "XT30XT30PW_MALE")
      (footprint "eagle-import:XT30PW_MALE")
      (libsource (lib "eagle-import") (part "XT30XT30PW_MALE"))
    )
    (comp (ref "J2")
      (value "XT30XT30PW_MALE")
      (footprint "eagle-import:XT30PW_MALE")
      (libsource (lib "eagle-import") (part "XT30XT30PW_MALE"))
    )
    (comp (ref "L1")
      (value "SRN4018-220M")
      (footprint "eagle-import:IND_BOURNS_SRN4018")
      (fields
        (field (name "MANUFACTURER_PART_NUMBER") "SRN4018220M")
        (field (name "MANUFACTURER_PART_NUMBER_1") "SRN4018-330M")
        (field (name "MPN") "SRN4018-330M")
      )
      (libsource (lib "eagle-import") (part "SRN4018-220M"))
    )
    (comp (ref "L2")
      (value "HALF_CHOKE")
      (footprint "eagle-import:1812_COMMON_HALF")
      (fields (field (name "MPN") "MF-RES-0805-0"))
      (libsource (lib "eagle-import") (part "HALF_CHOKE"))
    )
    (comp (ref "L3")
      (value "HALF_CHOKE")
      (footprint "eagle-import:1812_COMMON_HALF")
      (fields (field (name "MPN") "MF-RES-0805-0"))
      (libsource (lib "eagle-import") (part "HALF_CHOKE"))
    )
    (comp (ref "M1")
      (value "MOUNT")
      (footprint "eagle-import:M2.5MOUNT")
      (libsource (lib "eagle-import") (part "MOUNT"))
    )
    (comp (ref "M2")
      (value "MOUNT")
      (footprint "eagle-import:M2.5MOUNT")
      (libsource (lib "eagle-import") (part "MOUNT"))
    )
    (comp (ref "M3")
      (value "MOUNT")
      (footprint "eagle-import:M2.5MOUNT")
      (libsource (lib "eagle-import") (part "MOUNT"))
    )
    (comp (ref "M4")
      (value "MOUNT")
      (footprint "eagle-import:M2.5MOUNT")
      (libsource (lib "eagle-import") (part "MOUNT"))
    )
    (comp (ref "MOT1")
      (value "PAD24AWG_PAD")
      (footprint "eagle-import:24AWG_PAD")
      (libsource (lib "eagle-import") (part "PAD24AWG_PAD"))
    )
    (comp (ref "MOT2")
      (value "PAD24AWG_PAD")
      (footprint "eagle-import:24AWG_PAD")
      (libsource (lib "eagle-import") (part "PAD24AWG_PAD"))
    )
    (comp (ref "MOT3")
      (value "PAD24AWG_PAD")
      (footprint "eagle-import:24AWG_PAD")
      (libsource (lib "eagle-import") (part "PAD24AWG_PAD"))
    )
    (comp (ref "Q1")
      (value "TPH1R204PLSOP_ADVANCE_8")
      (footprint "eagle-import:SOP_ADVANCE_8")
      (fields
        (field (name "MF") "Toshiba")
        (field (name "MPN") "TPH1R204PL")
        (field (name "MF_1") "Toshiba")
        (field (name "MPN_1") "TPH2R506PL,L1Q")
      )
      (libsource (lib "eagle-import") (part "TPH1R204PLSOP_ADVANCE_8"))
    )
    (comp (ref "Q2")
      (value "TPH1R204PLSOP_ADVANCE_8")
      (footprint "eagle-import:SOP_ADVANCE_8")
      (fields
        (field (name "MF") "Toshiba")
        (field (name "MPN") "TPH1R204PL")
        (field (name "MF_1") "Toshiba")
        (field (name "MPN_1") "TPH2R506PL,L1Q")
      )
      (libsource (lib "eagle-import") (part "TPH1R204PLSOP_ADVANCE_8"))
    )
    (comp (ref "Q3")
      (value "TPH1R204PLSOP_ADVANCE_8")
      (footprint "eagle-import:SOP_ADVANCE_8")
      (fields
        (field (name "MF") "Toshiba")
        (field (name "MPN") "TPH1R204PL")
        (field (name "MF_1") "Toshiba")
        (field (name "MPN_1") "TPH2R506PL,L1Q")
      )
      (libsource (lib "eagle-import") (part "TPH1R204PLSOP_ADVANCE_8"))
    )
    (comp (ref "Q4")
      (value "TPH1R204PLSOP_ADVANCE_8")
      (footprint "eagle-import:SOP_ADVANCE_8")
      (fields
        (field (name "MF") "Toshiba")
        (field (name "MPN") "TPH1R204PL")
        (field (name "MF_1") "Toshiba")
        (field (name "MPN_1") "TPH2R506PL,L1Q")
      )
      (libsource (lib "eagle-import") (part "TPH1R204PLSOP_ADVANCE_8"))
    )
    (comp (ref "Q5")
      (value "TPH1R204PLSOP_ADVANCE_8")
      (footprint "eagle-import:SOP_ADVANCE_8")
      (fields
        (field (name "MF") "Toshiba")
        (field (name "MPN") "TPH1R204PL")
        (field (name "MF_1") "Toshiba")
        (field (name "MPN_1") "TPH2R506PL,L1Q")
      )
      (libsource (lib "eagle-import") (part "TPH1R204PLSOP_ADVANCE_8"))
    )
    (comp (ref "Q6")
      (value "TPH1R204PLSOP_ADVANCE_8")
      (footprint "eagle-import:SOP_ADVANCE_8")
      (fields
        (field (name "MF") "Toshiba")
        (field (name "MPN") "TPH1R204PL")
        (field (name "MF_1") "Toshiba")
        (field (name "MPN_1") "TPH2R506PL,L1Q")
      )
      (libsource (lib "eagle-import") (part "TPH1R204PLSOP_ADVANCE_8"))
    )
    (comp (ref "R1")
      (value "560")
      (footprint "eagle-import:R0402")
      (fields (field (name "HOUSEPART") "1") (field (name "MPN") "MF-RES-0402-560"))
      (libsource (lib "eagle-import") (part "mfpassives_RESISTOR_0402"))
    )
    (comp (ref "R2")
      (value "560")
      (footprint "eagle-import:R0402")
      (fields (field (name "HOUSEPART") "1") (field (name "MPN") "MF-RES-0402-560"))
      (libsource (lib "eagle-import") (part "mfpassives_RESISTOR_0402"))
    )
    (comp (ref "R3")
      (value "2k")
      (footprint "eagle-import:R0402")
      (fields (field (name "HOUSEPART") "YES") (field (name "MPN") "MF-RES-0402-2K"))
      (libsource (lib "eagle-import") (part "mfpassives_RESISTOR_0402"))
    )
    (comp (ref "R4")
      (value "2k")
      (footprint "eagle-import:R0402")
      (fields (field (name "HOUSEPART") "YES") (field (name "MPN") "MF-RES-0402-2K"))
      (libsource (lib "eagle-import") (part "mfpassives_RESISTOR_0402"))
    )
    (comp (ref "R5")
      (value "100k 1%")
      (footprint "eagle-import:R0402")
      (fields (field (name "MF") "Yageo") (field (name "MPN") "RC0402FR-07100KL"))
      (libsource (lib "eagle-import") (part "mfpassives_RESISTOR_0402"))
    )
    (comp (ref "R6")
      (value "4.7k 1%")
      (footprint "eagle-import:R0402")
      (fields (field (name "MF") "Yageo") (field (name "MPN") "RC0402FR-074K7L"))
      (libsource (lib "eagle-import") (part "mfpassives_RESISTOR_0402"))
    )
    (comp (ref "R7")
      (value "10k 1%")
      (footprint "eagle-import:R0402")
      (fields (field (name "MF") "Yageo") (field (name "MPN") "RC0402FR-0710KL"))
      (libsource (lib "eagle-import") (part "mfpassives_RESISTOR_0402"))
    )
    (comp (ref "R8")
      (value "47k NTC")
      (footprint "eagle-import:R0402")
      (fields (field (name "MF") "Murata") (field (name "MPN") "NCP15WB473F03RC"))
      (libsource (lib "eagle-import") (part "mfpassives_RESISTOR_0402"))
    )
    (comp (ref "R9")
      (value "10k 1%")
      (footprint "eagle-import:R0402")
      (fields (field (name "MF") "Yageo") (field (name "MPN") "RC0402FR-0710KL"))
      (libsource (lib "eagle-import") (part "mfpassives_RESISTOR_0402"))
    )
    (comp (ref "R10")
      (value "DNP")
      (footprint "eagle-import:R0402")
      (fields (field (name "POPULATE") "0"))
      (libsource (lib "eagle-import") (part "mfpassives_RESISTOR_0402"))
    )
    (comp (ref "R11")
      (value "DNP")
      (footprint "eagle-import:R0603")
      (fields (field (name "POPULATE") "0"))
      (libsource (lib "eagle-import") (part "mfpassives_RESISTOR_0603"))
    )
    (comp (ref "R12")
      (value "DNP")
      (footprint "eagle-import:R0603")
      (fields (field (name "POPULATE") "0"))
      (libsource (lib "eagle-import") (part "mfpassives_RESISTOR_0603"))
    )
    (comp (ref "R13")
      (value "2k")
      (footprint "eagle-import:R0402")
      (fields (field (name "HOUSEPART") "YES") (field (name "MPN") "MF-RES-0402-2K"))
      (libsource (lib "eagle-import") (part "mfpassives_RESISTOR_0402"))
    )
    (comp (ref "R14")
      (value "2k")
      (footprint "eagle-import:R0402")
      (fields (field (name "HOUSEPART") "YES") (field (name "MPN") "MF-RES-0402-2K"))
      (libsource (lib "eagle-import") (part "mfpassives_RESISTOR_0402"))
    )
    (comp (ref "R15")
      (value "22")
      (footprint "eagle-import:R0402_NOBORDER")
      (fields (field (name "HOUSEPART") "1") (field (name "MPN") "MF-RES-0402-22"))
      (libsource (lib "eagle-import") (part "RESISTOR_0402_NOBORDER"))
    )
    (comp (ref "R16")
      (value "22")
      (footprint "eagle-import:R0402_NOBORDER")
      (fields (field (name "HOUSEPART") "1") (field (name "MPN") "MF-RES-0402-22"))
      (libsource (lib "eagle-import") (part "RESISTOR_0402_NOBORDER"))
    )
    (comp (ref "R17")
      (value "22")
      (footprint "eagle-import:R0402_NOBORDER")
      (fields (field (name "HOUSEPART") "1") (field (name "MPN") "MF-RES-0402-22"))
      (libsource (lib "eagle-import") (part "RESISTOR_0402_NOBORDER"))
    )
    (comp (ref "R18")
      (value "DNP")
      (footprint "eagle-import:R0603")
      (fields (field (name "POPULATE") "0"))
      (libsource (lib "eagle-import") (part "mfpassives_RESISTOR_0603"))
    )
    (comp (ref "R19")
      (value "DNP")
      (footprint "eagle-import:R0603")
      (fields (field (name "POPULATE") "0"))
      (libsource (lib "eagle-import") (part "mfpassives_RESISTOR_0603"))
    )
    (comp (ref "R20")
      (value "DNP")
      (footprint "eagle-import:R0603")
      (fields (field (name "POPULATE") "0"))
      (libsource (lib "eagle-import") (part "mfpassives_RESISTOR_0603"))
    )
    (comp (ref "R21")
      (value "DNP")
      (footprint "eagle-import:R0603")
      (fields (field (name "POPULATE") "0"))
      (libsource (lib "eagle-import") (part "mfpassives_RESISTOR_0603"))
    )
    (comp (ref "R22")
      (value "0")
      (footprint "eagle-import:R0402")
      (fields (field (name "HOUSEPART") "1") (field (name "MPN") "MF-RES-0402-0"))
      (libsource (lib "eagle-import") (part "mfpassives_RESISTOR_0402"))
    )
    (comp (ref "R23")
      (value "0")
      (footprint "eagle-import:R0402")
      (fields (field (name "HOUSEPART") "1") (field (name "MPN") "MF-RES-0402-0"))
      (libsource (lib "eagle-import") (part "mfpassives_RESISTOR_0402"))
    )
    (comp (ref "R24")
      (value "0")
      (footprint "eagle-import:R0402")
      (fields (field (name "HOUSEPART") "1") (field (name "MPN") "MF-RES-0402-0"))
      (libsource (lib "eagle-import") (part "mfpassives_RESISTOR_0402"))
    )
    (comp (ref "R25")
      (value "0")
      (footprint "eagle-import:R0402")
      (fields (field (name "HOUSEPART") "1") (field (name "MPN") "MF-RES-0402-0"))
      (libsource (lib "eagle-import") (part "mfpassives_RESISTOR_0402"))
    )
    (comp (ref "R26")
      (value "0")
      (footprint "eagle-import:R0402")
      (fields (field (name "HOUSEPART") "1") (field (name "MPN") "MF-RES-0402-0"))
      (libsource (lib "eagle-import") (part "mfpassives_RESISTOR_0402"))
    )
    (comp (ref "R27")
      (value "0")
      (footprint "eagle-import:R0402")
      (fields (field (name "HOUSEPART") "1") (field (name "MPN") "MF-RES-0402-0"))
      (libsource (lib "eagle-import") (part "mfpassives_RESISTOR_0402"))
    )
    (comp (ref "RA")
      (value "0.5mOhm 1% 2W")
      (footprint "eagle-import:M1206")
      (fields (field (name "MF") "Stackpole Electronics") (field (name "MPN") "HCS1206FTL500"))
      (libsource (lib "eagle-import") (part "R-US_M1206"))
    )
    (comp (ref "RB")
      (value "0.5mOhm 1% 2W")
      (footprint "eagle-import:M1206")
      (fields (field (name "MF") "Stackpole Electronics") (field (name "MPN") "HCS1206FTL500"))
      (libsource (lib "eagle-import") (part "R-US_M1206"))
    )
    (comp (ref "RC")
      (value "0.5mOhm 1% 2W")
      (footprint "eagle-import:M1206")
      (fields (field (name "MF") "Stackpole Electronics") (field (name "MPN") "HCS1206FTL500"))
      (libsource (lib "eagle-import") (part "R-US_M1206"))
    )
    (comp (ref "SH1")
      (value "SHORTT5")
      (footprint "eagle-import:SHORT_TOP-50")
      (libsource (lib "eagle-import") (part "SHORTT5"))
    )
    (comp (ref "SH2")
      (value "SHORTT5")
      (footprint "eagle-import:SHORT_TOP-50")
      (libsource (lib "eagle-import") (part "SHORTT5"))
    )
    (comp (ref "SH3")
      (value "SHORTT5")
      (footprint "eagle-import:SHORT_TOP-50")
      (libsource (lib "eagle-import") (part "SHORTT5"))
    )
    (comp (ref "SH4")
      (value "SHORTMEDIUM")
      (footprint "eagle-import:SHORT_TOP-MEDIUM")
      (libsource (lib "eagle-import") (part "SHORTMEDIUM"))
    )
    (comp (ref "SWD")
      (value "JST-ZH6")
      (footprint "eagle-import:JST_S6B-ZR-SM4A-TF(LF)(SN)")
      (fields (field (name "MF") "JST") (field (name "MPN") "S6B-ZR-SM4A-TF(LF)(SN)"))
      (libsource (lib "eagle-import") (part "JST-ZH6"))
    )
    (comp (ref "TEMP1")
      (value "PAD24AWG_PAD")
      (footprint "eagle-import:24AWG_PAD")
      (libsource (lib "eagle-import") (part "PAD24AWG_PAD"))
    )
    (comp (ref "TEMP2")
      (value "PAD24AWG_PAD")
      (footprint "eagle-import:24AWG_PAD")
      (libsource (lib "eagle-import") (part "PAD24AWG_PAD"))
    )
    (comp (ref "U1")
      (value "STM32G474CEU6")
      (footprint "eagle-import:QFN50P700X700X60-49N")
      (fields (field (name "MOUSER_PART_NUMBER") "511-STM32G474CEU6"))
      (libsource (lib "eagle-import") (part "STM32G474CEU6"))
    )
    (comp (ref "U2")
      (value "TCAN334G")
      (footprint "eagle-import:SOIC8")
      (fields (field (name "MF") "TI") (field (name "MPN") "TCAN334GDCNT"))
      (libsource (lib "eagle-import") (part "TCAN334G"))
    )
    (comp (ref "U3")
      (value "AS5147")
      (footprint "eagle-import:TSSOP14")
      (fields (field (name "MF") "AMS") (field (name "MPN") "AS5047P-ATSM"))
      (libsource (lib "eagle-import") (part "AS5147"))
    )
    (comp (ref "U4")
      (value "MAX15062AATA+T")
      (footprint "eagle-import:21-0487A_MXM")
      (fields (field (name "COPYRIGHT") "Copyright (C) 2018 Accelerated Designs. All rights reserved"))
      (libsource (lib "eagle-import") (part "MAX15062AATA+T"))
    )
    (comp (ref "U5")
      (value "DRV8353S")
      (footprint "eagle-import:WQFN-40")
      (fields (field (name "MF") "TI") (field (name "MPN") "DRV8353FSRTAR"))
      (libsource (lib "eagle-import") (part "DRV8353S"))
    )
    (comp (ref "U6")
      (value "TCAN334GSOT23")
      (footprint "eagle-import:SOT23-8")
      (fields (field (name "MF") "TI") (field (name "MPN") "TCAN337GDR"))
      (libsource (lib "eagle-import") (part "TCAN334GSOT23"))
    )
  )
  (nets
    (net (code "1") (name "+3V3") (class "Default")
      (node (ref "ABS") (pin "1") (pinfunction "1_1") (pintype "passive"))
      (node (ref "C1") (pin "P$1") (pinfunction "P$1_P$1") (pintype "passive"))
      (node (ref "C10") (pin "P$1") (pinfunction "P$1_P$1") (pintype "passive"))
      (node (ref "C11") (pin "P$1") (pinfunction "P$1_P$1") (pintype "passive"))
      (node (ref "C12") (pin "P$1") (pinfunction "P$1_P$1") (pintype "passive"))
      (node (ref "C18") (pin "P$2") (pinfunction "P$2_P$2") (pintype "passive"))
      (node (ref "C2") (pin "P$1") (pinfunction "P$1_P$1") (pintype "passive"))
      (node (ref "C21") (pin "P$1") (pinfunction "P$1_P$1") (pintype "passive"))
      (node (ref "C4") (pin "P$1") (pinfunction "P$1_P$1") (pintype "passive"))
      (node (ref "C5") (pin "P$1") (pinfunction "P$1_P$1") (pintype "passive"))
      (node (ref "C56") (pin "P$1") (pinfunction "P$1_P$1") (pintype "passive"))
      (node (ref "C6") (pin "P$1") (pinfunction "P$1_P$1") (pintype "passive"))
      (node (ref "C7") (pin "P$2") (pinfunction "P$2_P$2") (pintype "passive"))
      (node (ref "C8") (pin "P$1") (pinfunction "P$1_P$1") (pintype "passive"))
      (node (ref "C9") (pin "P$1") (pinfunction "P$1_P$1") (pintype "passive"))
      (node (ref "D33") (pin "P$1") (pinfunction "P$1_P$1") (pintype "bidirectional"))
      (node (ref "ENC") (pin "1") (pinfunction "1_1") (pintype "passive"))
      (node (ref "L1") (pin "1") (pinfunction "1_1") (pintype "passive"))
      (node (ref "R1") (pin "P$1") (pinfunction "P$1_P$1") (pintype "passive"))
      (node (ref "R13") (pin "P$1") (pinfunction "P$1_P$1") (pintype "passive"))
      (node (ref "R14") (pin "P$1") (pinfunction "P$1_P$1") (pintype "passive"))
      (node (ref "R2") (pin "P$1") (pinfunction "P$1_P$1") (pintype "passive"))
      (node (ref "R3") (pin "P$1") (pinfunction "P$1_P$1") (pintype "passive"))
      (node (ref "R4") (pin "P$1") (pinfunction "P$1_P$1") (pintype "passive"))
      (node (ref "R8") (pin "P$1") (pinfunction "P$1_P$1") (pintype "passive"))
      (node (ref "SWD") (pin "6") (pinfunction "6_6") (pintype "passive"))
      (node (ref "TEMP1") (pin "P$1") (pinfunction "P$1_P$1") (pintype "bidirectional"))
      (node (ref "U1") (pin "1") (pinfunction "VBAT_1") (pintype "bidirectional"))
      (node (ref "U1") (pin "20") (pinfunction "VREF+_20") (pintype "bidirectional"))
      (node (ref "U1") (pin "21") (pinfunction "VDDA_21") (pintype "bidirectional"))
      (node (ref "U1") (pin "23") (pinfunction "VDD_1_23") (pintype "bidirectional"))
      (node (ref "U1") (pin "35") (pinfunction "VDD_2_35") (pintype "bidirectional"))
      (node (ref "U1") (pin "48") (pinfunction "VDD_3_48") (pintype "bidirectional"))
      (node (ref "U2") (pin "3") (pinfunction "VCC_3") (pintype "power_in"))
      (node (ref "U3") (pin "12") (pinfunction "VDD3V_12") (pintype "bidirectional"))
      (node (ref "U4") (pin "4") (pinfunction "FB/VOUT_4") (pintype "bidirectional"))
      (node (ref "U5") (pin "24") (pinfunction "VREF_24") (pintype "bidirectional"))
      (node (ref "U6") (pin "3") (pinfunction "VCC_3") (pintype "power_in"))
    )
    (net (code "2") (name "/AS5047_A") (class "Default")
      (node (ref "U1") (pin "43") (pinfunction "PB5_43") (pintype "bidirectional"))
      (node (ref "U3") (pin "7") (pinfunction "A_7") (pintype "bidirectional"))
    )
    (net (code "3") (name "/AS5047_B") (class "Default")
      (node (ref "U1") (pin "42") (pinfunction "PB4_42") (pintype "bidirectional"))
      (node (ref "U3") (pin "6") (pinfunction "B_6") (pintype "bidirectional"))
    )
    (net (code "4") (name "/AS5047_CS") (class "Default")
      (node (ref "U1") (pin "24") (pinfunction "PB11_24") (pintype "bidirectional"))
      (node (ref "U3") (pin "1") (pinfunction "CS/_1") (pintype "bidirectional"))
    )
    (net (code "5") (name "/AS5047_MISO") (class "Default")
      (node (ref "ENC") (pin "5") (pinfunction "5_5") (pintype "passive"))
      (node (ref "U1") (pin "27") (pinfunction "PB14_27") (pintype "bidirectional"))
      (node (ref "U3") (pin "3") (pinfunction "MISO_3") (pintype "bidirectional"))
    )
    (net (code "6") (name "/AS5047_MOSI") (class "Default")
      (node (ref "ENC") (pin "6") (pinfunction "6_6") (pintype "passive"))
      (node (ref "U1") (pin "28") (pinfunction "PB15_28") (pintype "bidirectional"))
      (node (ref "U3") (pin "4") (pinfunction "MOSI_4") (pintype "bidirectional"))
    )
    (net (code "7") (name "/AS5047_SCK") (class "Default")
      (node (ref "ENC") (pin "4") (pinfunction "4_4") (pintype "passive"))
      (node (ref "U1") (pin "26") (pinfunction "PB13_26") (pintype "bidirectional"))
      (node (ref "U3") (pin "2") (pinfunction "CLK_2") (pintype "bidirectional"))
    )
    (net (code "8") (name "/CAN2_N") (class "Default")
      (node (ref "L2") (pin "P$2") (pinfunction "2_P$2") (pintype "passive"))
      (node (ref "U2") (pin "6") (pinfunction "CANL_6") (pintype "bidirectional"))
      (node (ref "U6") (pin "6") (pinfunction "CANL_6") (pintype "bidirectional"))
    )
    (net (code "9") (name "/CAN2_P") (class "Default")
      (node (ref "L3") (pin "P$2") (pinfunction "2_P$2") (pintype "passive"))
      (node (ref "U2") (pin "7") (pinfunction "CANH_7") (pintype "bidirectional"))
      (node (ref "U6") (pin "7") (pinfunction "CANH_7") (pintype "bidirectional"))
    )
    (net (code "10") (name "/CAN_N") (class "Default")
      (node (ref "CAN1") (pin "2") (pinfunction "2_2") (pintype "passive"))
      (node (ref "CAN2") (pin "2") (pinfunction "2_2") (pintype "passive"))
      (node (ref "D4") (pin "2") (pinfunction "2_2") (pintype "bidirectional"))
      (node (ref "L2") (pin "P$1") (pinfunction "1_P$1") (pintype "passive"))
    )
    (net (code "11") (name "/CAN_P") (class "Default")
      (node (ref "CAN1") (pin "1") (pinfunction "1_1") (pintype "passive"))
      (node (ref "CAN2") (pin "1") (pinfunction "1_1") (pintype "passive"))
      (node (ref "D4") (pin "1") (pinfunction "1_1") (pintype "bidirectional"))
      (node (ref "L3") (pin "P$1") (pinfunction "1_P$1") (pintype "passive"))
    )
    (net (code "12") (name "/CAN_RX") (class "Default")
      (node (ref "U1") (pin "33") (pinfunction "PA11_33") (pintype "bidirectional"))
      (node (ref "U2") (pin "4") (pinfunction "RXD_4") (pintype "output"))
      (node (ref "U6") (pin "4") (pinfunction "RXD_4") (pintype "output"))
    )
    (net (code "13") (name "/CAN_TX") (class "Default")
      (node (ref "U1") (pin "34") (pinfunction "PA12_34") (pintype "bidirectional"))
      (node (ref "U2") (pin "1") (pinfunction "TXD_1") (pintype "input"))
      (node (ref "U6") (pin "1") (pinfunction "TXD_1") (pintype "input"))
    )
    (net (code "14") (name "/CUR1") (class "Default")
      (node (ref "R15") (pin "P$1") (pinfunction "P$1_P$1") (pintype "passive"))
      (node (ref "U5") (pin "23") (pinfunction "SOA_23") (pintype "bidirectional"))
    )
    (net (code "15") (name "/CUR2") (class "Default")
      (node (ref "R16") (pin "P$1") (pinfunction "P$1_P$1") (pintype "passive"))
      (node (ref "U5") (pin "22") (pinfunction "SOB_22") (pintype "bidirectional"))
    )
    (net (code "16") (name "/CUR3") (class "Default")
      (node (ref "R17") (pin "P$1") (pinfunction "P$1_P$1") (pintype "passive"))
      (node (ref "U5") (pin "21") (pinfunction "SOC_21") (pintype "bidirectional"))
    )
    (net (code "17") (name "/DAC") (class "Default")
      (node (ref "DAC") (pin "P$1") (pinfunction "P$1_P$1") (pintype "bidirectional"))
      (node (ref "U1") (pin "12") (pinfunction "PA4_12") (pintype "bidirectional"))
    )
    (net (code "18") (name "/DEBUG1") (class "Default")
      (node (ref "DBG1") (pin "P$1") (pinfunction "P$1_P$1") (pintype "bidirectional"))
      (node (ref "U1") (pin "3") (pinfunction "PC14-OSC32_IN_3") (pintype "bidirectional"))
    )
    (net (code "19") (name "/DEBUG2") (class "Default")
      (node (ref "DBG2") (pin "P$1") (pinfunction "P$1_P$1") (pintype "bidirectional"))
      (node (ref "U1") (pin "4") (pinfunction "PC15-OSC32_OUT_4") (pintype "bidirectional"))
    )
    (net (code "20") (name "/DEBUG_RX") (class "Default")
      (node (ref "DTR") (pin "P$1") (pinfunction "P$1_P$1") (pintype "bidirectional"))
      (node (ref "U1") (pin "40") (pinfunction "PC11_40") (pintype "bidirectional"))
    )
    (net (code "21") (name "/DEBUG_TX") (class "Default")
      (node (ref "DTX") (pin "P$1") (pinfunction "P$1_P$1") (pintype "bidirectional"))
      (node (ref "U1") (pin "39") (pinfunction "PC10_39") (pintype "bidirectional"))
    )
    (net (code "22") (name "/DRV8323_CS") (class "Default")
      (node (ref "DRV_CS") (pin "P$1") (pinfunction "P$1_P$1") (pintype "bidirectional"))
      (node (ref "U1") (pin "16") (pinfunction "PC4_16") (pintype "bidirectional"))
      (node (ref "U5") (pin "30") (pinfunction "CS_30") (pintype "bidirectional"))
    )
    (net (code "23") (name "/DRV8323_MISO") (class "Default")
      (node (ref "DRV_MISO") (pin "P$1") (pinfunction "P$1_P$1") (pintype "bidirectional"))
      (node (ref "R13") (pin "P$2") (pinfunction "P$2_P$2") (pintype "passive"))
      (node (ref "U1") (pin "14") (pinfunction "PA6_14") (pintype "bidirectional"))
      (node (ref "U5") (pin "27") (pinfunction "MISO_27") (pintype "bidirectional"))
    )
    (net (code "24") (name "/DRV8323_MOSI") (class "Default")
      (node (ref "DRV_MOSI") (pin "P$1") (pinfunction "P$1_P$1") (pintype "bidirectional"))
      (node (ref "U1") (pin "15") (pinfunction "PA7_15") (pintype "bidirectional"))
      (node (ref "U5") (pin "28") (pinfunction "MOSI_28") (pintype "bidirectional"))
    )
    (net (code "25") (name "/DRV8323_SCLK") (class "Default")
      (node (ref "DRV_SCK") (pin "P$1") (pinfunction "P$1_P$1") (pintype "bidirectional"))
      (node (ref "U1") (pin "13") (pinfunction "PA5_13") (pintype "bidirectional"))
      (node (ref "U5") (pin "29") (pinfunction "SCLK_29") (pintype "bidirectional"))
    )
    (net (code "26") (name "/FCUR1") (class "Default")
      (node (ref "C58") (pin "P$1") (pinfunction "P$1_P$1") (pintype "passive"))
      (node (ref "R15") (pin "P$2") (pinfunction "P$2_P$2") (pintype "passive"))
      (node (ref "U1") (pin "17") (pinfunction "PB0_17") (pintype "bidirectional"))
    )
    (net (code "27") (name "/FCUR2") (class "Default")
      (node (ref "C59") (pin "P$1") (pinfunction "P$1_P$1") (pintype "passive"))
      (node (ref "R16") (pin "P$2") (pinfunction "P$2_P$2") (pintype "passive"))
      (node (ref "U1") (pin "18") (pinfunction "PB1_18") (pintype "bidirectional"))
    )
    (net (code "28") (name "/FCUR3") (class "Default")
      (node (ref "C60") (pin "P$1") (pinfunction "P$1_P$1") (pintype "passive"))
      (node (ref "R17") (pin "P$2") (pinfunction "P$2_P$2") (pintype "passive"))
      (node (ref "U1") (pin "19") (pinfunction "PB2_19") (pintype "bidirectional"))
    )
    (net (code "29") (name "/GHA") (class "Default")
      (node (ref "D10") (pin "1") (pinfunction "K_1") (pintype "bidirectional"))
      (node (ref "R22") (pin "P$1") (pinfunction "P$1_P$1") (pintype "passive"))
      (node (ref "U5") (pin "6") (pinfunction "GHA_6") (pintype "bidirectional"))
    )
    (net (code "30") (name "/GHA_D") (class "Default")
      (node (ref "D10") (pin "2") (pinfunction "A_2") (pintype "bidirectional"))
      (node (ref "Q1") (pin "4") (pinfunction "G_4") (pintype "passive"))
      (node (ref "R22") (pin "P$2") (pinfunction "P$2_P$2") (pintype "passive"))
    )
    (net (code "31") (name "/GHB") (class "Default")
      (node (ref "D11") (pin "1") (pinfunction "K_1") (pintype "bidirectional"))
      (node (ref "R24") (pin "P$1") (pinfunction "P$1_P$1") (pintype "passive"))
      (node (ref "U5") (pin "15") (pinfunction "GHB_15") (pintype "bidirectional"))
    )
    (net (code "32") (name "/GHB_D") (class "Default")
      (node (ref "D11") (pin "2") (pinfunction "A_2") (pintype "bidirectional"))
      (node (ref "Q3") (pin "4") (pinfunction "G_4") (pintype "passive"))
      (node (ref "R24") (pin "P$2") (pinfunction "P$2_P$2") (pintype "passive"))
    )
    (net (code "33") (name "/GHC") (class "Default")
      (node (ref "D12") (pin "1") (pinfunction "K_1") (pintype "bidirectional"))
      (node (ref "R26") (pin "P$1") (pinfunction "P$1_P$1") (pintype "passive"))
      (node (ref "U5") (pin "16") (pinfunction "GHC_16") (pintype "bidirectional"))
    )
    (net (code "34") (name "/GHC_D") (class "Default")
      (node (ref "D12") (pin "2") (pinfunction "A_2") (pintype "bidirectional"))
      (node (ref "Q5") (pin "4") (pinfunction "G_4") (pintype "passive"))
      (node (ref "R26") (pin "P$2") (pinfunction "P$2_P$2") (pintype "passive"))
    )
    (net (code "35") (name "/GLA") (class "Default")
      (node (ref "D7") (pin "1") (pinfunction "K_1") (pintype "bidirectional"))
      (node (ref "R23") (pin "P$1") (pinfunction "P$1_P$1") (pintype "passive"))
      (node (ref "U5") (pin "8") (pinfunction "GLA_8") (pintype "bidirectional"))
    )
    (net (code "36") (name "/GLA_D") (class "Default")
      (node (ref "D1") (pin "1") (pinfunction "K_1") (pintype "bidirectional"))
      (node (ref "D7") (pin "2") (pinfunction "A_2") (pintype "bidirectional"))
      (node (ref "Q2") (pin "4") (pinfunction "G_4") (pintype "passive"))
      (node (ref "R23") (pin "P$2") (pinfunction "P$2_P$2") (pintype "passive"))
    )
    (net (code "37") (name "/GLB") (class "Default")
      (node (ref "D8") (pin "1") (pinfunction "K_1") (pintype "bidirectional"))
      (node (ref "R25") (pin "P$1") (pinfunction "P$1_P$1") (pintype "passive"))
      (node (ref "U5") (pin "13") (pinfunction "GLB_13") (pintype "bidirectional"))
    )
    (net (code "38") (name "/GLB_D") (class "Default")
      (node (ref "D5") (pin "1") (pinfunction "K_1") (pintype "bidirectional"))
      (node (ref "D8") (pin "2") (pinfunction "A_2") (pintype "bidirectional"))
      (node (ref "Q4") (pin "4") (pinfunction "G_4") (pintype "passive"))
      (node (ref "R25") (pin "P$2") (pinfunction "P$2_P$2") (pintype "passive"))
    )
    (net (code "39") (name "/GLC") (class "Default")
      (node (ref "D9") (pin "1") (pinfunction "K_1") (pintype "bidirectional"))
      (node (ref "R27") (pin "P$1") (pinfunction "P$1_P$1") (pintype "passive"))
      (node (ref "U5") (pin "18") (pinfunction "GLC_18") (pintype "bidirectional"))
    )
    (net (code "40") (name "/GLC_D") (class "Default")
      (node (ref "D6") (pin "1") (pinfunction "K_1") (pintype "bidirectional"))
      (node (ref "D9") (pin "2") (pinfunction "A_2") (pintype "bidirectional"))
      (node (ref "Q6") (pin "4") (pinfunction "G_4") (pintype "passive"))
      (node (ref "R27") (pin "P$2") (pinfunction "P$2_P$2") (pintype "passive"))
    )
    (net (code "41") (name "/I2C_ABS_SCL") (class "Default")
      (node (ref "ABS") (pin "2") (pinfunction "2_2") (pintype "passive"))
      (node (ref "R4") (pin "P$2") (pinfunction "P$2_P$2") (pintype "passive"))
      (node (ref "U1") (pin "46") (pinfunction "PB8-BOOT0_46") (pintype "bidirectional"))
    )
    (net (code "42") (name "/I2C_ABS_SDA") (class "Default")
      (node (ref "ABS") (pin "3") (pinfunction "3_3") (pintype "passive"))
      (node (ref "R3") (pin "P$2") (pinfunction "P$2_P$2") (pintype "passive"))
      (node (ref "U1") (pin "47") (pinfunction "PB9_47") (pintype "bidirectional"))
    )
    (net (code "43") (name "/LED1") (class "Default")
      (node (ref "D3") (pin "CATHODE") (pinfunction "CATHODE_CATHODE") (pintype "power_in"))
      (node (ref "U1") (pin "5") (pinfunction "PF0-OSC_IN_5") (pintype "bidirectional"))
    )
    (net (code "44") (name "/LED2") (class "Default")
      (node (ref "D2") (pin "CATHODE") (pinfunction "CATHODE_CATHODE") (pintype "power_in"))
      (node (ref "U1") (pin "6") (pinfunction "PF1-OSC_OUT_6") (pintype "bidirectional"))
    )
    (net (code "45") (name "/MOTOR1") (class "Default")
      (node (ref "MOT1") (pin "P$1") (pinfunction "P$1_P$1") (pintype "bidirectional"))
      (node (ref "U1") (pin "8") (pinfunction "PA0_8") (pintype "bidirectional"))
      (node (ref "U5") (pin "32") (pinfunction "INHA_32") (pintype "bidirectional"))
    )
    (net (code "46") (name "/MOTOR2") (class "Default")
      (node (ref "MOT2") (pin "P$1") (pinfunction "P$1_P$1") (pintype "bidirectional"))
      (node (ref "U1") (pin "9") (pinfunction "PA1_9") (pintype "bidirectional"))
      (node (ref "U5") (pin "34") (pinfunction "INHB_34") (pintype "bidirectional"))
    )
    (net (code "47") (name "/MOTOR3") (class "Default")
      (node (ref "MOT3") (pin "P$1") (pinfunction "P$1_P$1") (pintype "bidirectional"))
      (node (ref "U1") (pin "10") (pinfunction "PA2_10") (pintype "bidirectional"))
      (node (ref "U5") (pin "36") (pinfunction "INHC_36") (pintype "bidirectional"))
    )
    (net (code "48") (name "/MOTOR_ENABLE") (class "Default")
      (node (ref "U1") (pin "11") (pinfunction "PA3_11") (pintype "bidirectional"))
      (node (ref "U5") (pin "31") (pinfunction "ENABLE_31") (pintype "bidirectional"))
    )
    (net (code "49") (name "/MOTOR_FAULT") (class "Default")
      (node (ref "R14") (pin "P$2") (pinfunction "P$2_P$2") (pintype "passive"))
      (node (ref "U1") (pin "44") (pinfunction "PB6_44") (pintype "bidirectional"))
      (node (ref "U5") (pin "26") (pinfunction "FAULT_26") (pintype "bidirectional"))
    )
    (net (code "50") (name "/MOTOR_HIZ") (class "Default")
      (node (ref "U1") (pin "45") (pinfunction "PB7_45") (pintype "bidirectional"))
      (node (ref "U5") (pin "33") (pinfunction "INLA_33") (pintype "bidirectional"))
      (node (ref "U5") (pin "35") (pinfunction "INLB_35") (pintype "bidirectional"))
      (node (ref "U5") (pin "37") (pinfunction "INLC_37") (pintype "bidirectional"))
    )
    (net (code "51") (name "/NRST") (class "Default")
      (node (ref "C3") (pin "P$1") (pinfunction "P$1_P$1") (pintype "passive"))
      (node (ref "SWD") (pin "2") (pinfunction "2_2") (pintype "passive"))
      (node (ref "U1") (pin "7") (pinfunction "PG10-NRST_7") (pintype "bidirectional"))
    )
    (net (code "52") (name "/SECONDARY_ENC_CS") (class "Default")
      (node (ref "ENC") (pin "2") (pinfunction "2_2") (pintype "passive"))
      (node (ref "U1") (pin "2") (pinfunction "PC13_2") (pintype "bidirectional"))
    )
    (net (code "53") (name "/SHA") (class "Default")
      (node (ref "A") (pin "1") (pinfunction "P$1_1") (pintype "bidirectional"))
      (node (ref "C64") (pin "P$2") (pinfunction "P$2_P$2") (pintype "passive"))
      (node (ref "C65") (pin "P$1") (pinfunction "P$1_P$1") (pintype "passive"))
      (node (ref "DA") (pin "P$1") (pinfunction "P$1_P$1") (pintype "bidirectional"))
      (node (ref "Q1") (pin "1") (pinfunction "S_1") (pintype "passive"))
      (node (ref "Q1") (pin "2") (pinfunction "S_2") (pintype "passive"))
      (node (ref "Q1") (pin "3") (pinfunction "S_3") (pintype "passive"))
      (node (ref "Q2") (pin "5") (pinfunction "D_5") (pintype "passive"))
      (node (ref "Q2") (pin "6") (pinfunction "D_6") (pintype "passive"))
      (node (ref "Q2") (pin "7") (pinfunction "D_7") (pintype "passive"))
      (node (ref "Q2") (pin "8") (pinfunction "D_8") (pintype "passive"))
      (node (ref "Q2") (pin "PAD") (pinfunction "D_PAD") (pintype "passive"))
      (node (ref "U5") (pin "7") (pinfunction "SHA_7") (pintype "bidirectional"))
    )
    (net (code "54") (name "/SHB") (class "Default")
      (node (ref "B") (pin "1") (pinfunction "P$1_1") (pintype "bidirectional"))
      (node (ref "C66") (pin "P$2") (pinfunction "P$2_P$2") (pintype "passive"))
      (node (ref "C67") (pin "P$1") (pinfunction "P$1_P$1") (pintype "passive"))
      (node (ref "DB") (pin "P$1") (pinfunction "P$1_P$1") (pintype "bidirectional"))
      (node (ref "Q3") (pin "1") (pinfunction "S_1") (pintype "passive"))
      (node (ref "Q3") (pin "2") (pinfunction "S_2") (pintype "passive"))
      (node (ref "Q3") (pin "3") (pinfunction "S_3") (pintype "passive"))
      (node (ref "Q4") (pin "5") (pinfunction "D_5") (pintype "passive"))
      (node (ref "Q4") (pin "6") (pinfunction "D_6") (pintype "passive"))
      (node (ref "Q4") (pin "7") (pinfunction "D_7") (pintype "passive"))
      (node (ref "Q4") (pin "8") (pinfunction "D_8") (pintype "passive"))
      (node (ref "Q4") (pin "PAD") (pinfunction "D_PAD") (pintype "passive"))
      (node (ref "U5") (pin "14") (pinfunction "SHB_14") (pintype "bidirectional"))
    )
    (net (code "55") (name "/SHC") (class "Default")
      (node (ref "C") (pin "1") (pinfunction "P$1_1") (pintype "bidirectional"))
      (node (ref "C68") (pin "P$2") (pinfunction "P$2_P$2") (pintype "passive"))
      (node (ref "C69") (pin "P$1") (pinfunction "P$1_P$1") (pintype "passive"))
      (node (ref "DC") (pin "P$1") (pinfunction "P$1_P$1") (pintype "bidirectional"))
      (node (ref "Q5") (pin "1") (pinfunction "S_1") (pintype "passive"))
      (node (ref "Q5") (pin "2") (pinfunction "S_2") (pintype "passive"))
      (node (ref "Q5") (pin "3") (pinfunction "S_3") (pintype "passive"))
      (node (ref "Q6") (pin "5") (pinfunction "D_5") (pintype "passive"))
      (node (ref "Q6") (pin "6") (pinfunction "D_6") (pintype "passive"))
      (node (ref "Q6") (pin "7") (pinfunction "D_7") (pintype "passive"))
      (node (ref "Q6") (pin "8") (pinfunction "D_8") (pintype "passive"))
      (node (ref "Q6") (pin "PAD") (pinfunction "D_PAD") (pintype "passive"))
      (node (ref "U5") (pin "17") (pinfunction "SHC_17") (pintype "bidirectional"))
    )
    (net (code "56") (name "/SWCLK") (class "Default")
      (node (ref "SWD") (pin "5") (pinfunction "5_5") (pintype "passive"))
      (node (ref "U1") (pin "37") (pinfunction "PA14_37") (pintype "bidirectional"))
    )
    (net (code "57") (name "/SWDIO") (class "Default")
      (node (ref "SWD") (pin "3") (pinfunction "3_3") (pintype "passive"))
      (node (ref "U1") (pin "36") (pinfunction "PA13_36") (pintype "bidirectional"))
    )
    (net (code "58") (name "/SXA_N") (class "Default")
      (node (ref "SH1") (pin "1") (pinfunction "P$1_1") (pintype "bidirectional"))
      (node (ref "U5") (pin "10") (pinfunction "SNA_10") (pintype "bidirectional"))
    )
    (net (code "59") (name "/SXA_P") (class "Default")
      (node (ref "C61") (pin "P$2") (pinfunction "P$2_P$2") (pintype "passive"))
      (node (ref "Q2") (pin "1") (pinfunction "S_1") (pintype "passive"))
      (node (ref "Q2") (pin "2") (pinfunction "S_2") (pintype "passive"))
      (node (ref "Q2") (pin "3") (pinfunction "S_3") (pintype "passive"))
      (node (ref "R12") (pin "P$2") (pinfunction "P$2_P$2") (pintype "passive"))
      (node (ref "RA") (pin "2") (pinfunction "2_2") (pintype "passive"))
      (node (ref "U5") (pin "9") (pinfunction "SPA_9") (pintype "bidirectional"))
    )
    (net (code "60") (name "/SXB_N") (class "Default")
      (node (ref "SH2") (pin "1") (pinfunction "P$1_1") (pintype "bidirectional"))
      (node (ref "U5") (pin "11") (pinfunction "SNB_11") (pintype "bidirectional"))
    )
    (net (code "61") (name "/SXB_P") (class "Default")
      (node (ref "C62") (pin "P$2") (pinfunction "P$2_P$2") (pintype "passive"))
      (node (ref "Q4") (pin "1") (pinfunction "S_1") (pintype "passive"))
      (node (ref "Q4") (pin "2") (pinfunction "S_2") (pintype "passive"))
      (node (ref "Q4") (pin "3") (pinfunction "S_3") (pintype "passive"))
      (node (ref "R19") (pin "P$2") (pinfunction "P$2_P$2") (pintype "passive"))
      (node (ref "RB") (pin "2") (pinfunction "2_2") (pintype "passive"))
      (node (ref "U5") (pin "12") (pinfunction "SPB_12") (pintype "bidirectional"))
    )
    (net (code "62") (name "/SXC_N") (class "Default")
      (node (ref "SH3") (pin "1") (pinfunction "P$1_1") (pintype "bidirectional"))
      (node (ref "U5") (pin "20") (pinfunction "SNC_20") (pintype "bidirectional"))
    )
    (net (code "63") (name "/SXC_P") (class "Default")
      (node (ref "C63") (pin "P$2") (pinfunction "P$2_P$2") (pintype "passive"))
      (node (ref "Q6") (pin "1") (pinfunction "S_1") (pintype "passive"))
      (node (ref "Q6") (pin "2") (pinfunction "S_2") (pintype "passive"))
      (node (ref "Q6") (pin "3") (pinfunction "S_3") (pintype "passive"))
      (node (ref "R21") (pin "P$2") (pinfunction "P$2_P$2") (pintype "passive"))
      (node (ref "RC") (pin "2") (pinfunction "2_2") (pintype "passive"))
      (node (ref "U5") (pin "19") (pinfunction "SPC_19") (pintype "bidirectional"))
    )
    (net (code "64") (name "/VBAT_SENSE") (class "Default")
      (node (ref "C57") (pin "P$1") (pinfunction "P$1_P$1") (pintype "passive"))
      (node (ref "R5") (pin "P$1") (pinfunction "P$1_P$1") (pintype "passive"))
      (node (ref "R6") (pin "P$2") (pinfunction "P$2_P$2") (pintype "passive"))
      (node (ref "U1") (pin "25") (pinfunction "PB12_25") (pintype "bidirectional"))
    )
    (net (code "65") (name "/VSW") (class "Default")
      (node (ref "L1") (pin "2") (pinfunction "2_2") (pintype "passive"))
      (node (ref "U4") (pin "8") (pinfunction "LX_8") (pintype "passive"))
    )
    (net (code "66") (name "/VTEMP_FET") (class "Default")
      (node (ref "C13") (pin "P$1") (pinfunction "P$1_P$1") (pintype "passive"))
      (node (ref "R8") (pin "P$2") (pinfunction "P$2_P$2") (pintype "passive"))
      (node (ref "R9") (pin "P$1") (pinfunction "P$1_P$1") (pintype "passive"))
      (node (ref "U1") (pin "31") (pinfunction "PA9_31") (pintype "bidirectional"))
    )
    (net (code "67") (name "/VTEMP_MOT") (class "Default")
      (node (ref "R7") (pin "P$1") (pinfunction "P$1_P$1") (pintype "passive"))
      (node (ref "TEMP2") (pin "P$1") (pinfunction "P$1_P$1") (pintype "bidirectional"))
      (node (ref "U1") (pin "30") (pinfunction "PA8_30") (pintype "bidirectional"))
    )
    (net (code "68") (name "GND") (class "Default")
      (node (ref "ABS") (pin "4") (pinfunction "4_4") (pintype "passive"))
      (node (ref "C1") (pin "P$2") (pinfunction "P$2_P$2") (pintype "passive"))
      (node (ref "C10") (pin "P$2") (pinfunction "P$2_P$2") (pintype "passive"))
      (node (ref "C11") (pin "P$2") (pinfunction "P$2_P$2") (pintype "passive"))
      (node (ref "C12") (pin "P$2") (pinfunction "P$2_P$2") (pintype "passive"))
      (node (ref "C13") (pin "P$2") (pinfunction "P$2_P$2") (pintype "passive"))
      (node (ref "C18") (pin "P$1") (pinfunction "P$1_P$1") (pintype "passive"))
      (node (ref "C2") (pin "P$2") (pinfunction "P$2_P$2") (pintype "passive"))
      (node (ref "C20") (pin "P$2") (pinfunction "P$2_P$2") (pintype "passive"))
      (node (ref "C21") (pin "P$2") (pinfunction "P$2_P$2") (pintype "passive"))
      (node (ref "C3") (pin "P$2") (pinfunction "P$2_P$2") (pintype "passive"))
      (node (ref "C4") (pin "P$2") (pinfunction "P$2_P$2") (pintype "passive"))
      (node (ref "C5") (pin "P$2") (pinfunction "P$2_P$2") (pintype "passive"))
      (node (ref "C56") (pin "P$2") (pinfunction "P$2_P$2") (pintype "passive"))
      (node (ref "C57") (pin "P$2") (pinfunction "P$2_P$2") (pintype "passive"))
      (node (ref "C58") (pin "P$2") (pinfunction "P$2_P$2") (pintype "passive"))
      (node (ref "C59") (pin "P$2") (pinfunction "P$2_P$2") (pintype "passive"))
      (node (ref "C6") (pin "P$2") (pinfunction "P$2_P$2") (pintype "passive"))
      (node (ref "C60") (pin "P$2") (pinfunction "P$2_P$2") (pintype "passive"))
      (node (ref "C7") (pin "P$1") (pinfunction "P$1_P$1") (pintype "passive"))
      (node (ref "C8") (pin "P$2") (pinfunction "P$2_P$2") (pintype "passive"))
      (node (ref "C9") (pin "P$2") (pinfunction "P$2_P$2") (pintype "passive"))
      (node (ref "CAN1") (pin "3") (pinfunction "3_3") (pintype "passive"))
      (node (ref "CAN2") (pin "3") (pinfunction "3_3") (pintype "passive"))
      (node (ref "D4") (pin "3") (pinfunction "3_3") (pintype "bidirectional"))
      (node (ref "DG1") (pin "P$1") (pinfunction "P$1_P$1") (pintype "bidirectional"))
      (node (ref "DG2") (pin "P$1") (pinfunction "P$1_P$1") (pintype "bidirectional"))
      (node (ref "ENC") (pin "3") (pinfunction "3_3") (pintype "passive"))
      (node (ref "R6") (pin "P$1") (pinfunction "P$1_P$1") (pintype "passive"))
      (node (ref "R7") (pin "P$2") (pinfunction "P$2_P$2") (pintype "passive"))
      (node (ref "R9") (pin "P$2") (pinfunction "P$2_P$2") (pintype "passive"))
      (node (ref "SH4") (pin "2") (pinfunction "P$2_2") (pintype "bidirectional"))
      (node (ref "SWD") (pin "4") (pinfunction "4_4") (pintype "passive"))
      (node (ref "U1") (pin "32") (pinfunction "PA10_32") (pintype "bidirectional"))
      (node (ref "U1") (pin "49") (pinfunction "THERMALPAD_49") (pintype "bidirectional"))
      (node (ref "U2") (pin "2") (pinfunction "GND_2") (pintype "power_in"))
      (node (ref "U2") (pin "5") (pinfunction "SHDN_5") (pintype "input"))
      (node (ref "U2") (pin "8") (pinfunction "STB_8") (pintype "input"))
      (node (ref "U3") (pin "13") (pinfunction "GND_13") (pintype "bidirectional"))
      (node (ref "U3") (pin "5") (pinfunction "TEST_5") (pintype "bidirectional"))
      (node (ref "U4") (pin "7") (pinfunction "GND_7") (pintype "power_in"))
      (node (ref "U5") (pin "25") (pinfunction "AGND_25") (pintype "bidirectional"))
      (node (ref "U6") (pin "2") (pinfunction "GND_2") (pintype "power_in"))
      (node (ref "U6") (pin "5") (pinfunction "SHDN_5") (pintype "input"))
      (node (ref "U6") (pin "8") (pinfunction "STB_8") (pintype "input"))
    )
    (net (code "69") (name "Net-(C55-PadP$1)") (class "Default")
      (node (ref "C55") (pin "P$1") (pinfunction "P$1_P$1") (pintype "passive"))
      (node (ref "M3") (pin "P$1") (pinfunction "P$1_P$1") (pintype "bidirectional"))
      (node (ref "R10") (pin "P$1") (pinfunction "P$1_P$1") (pintype "passive"))
    )
    (net (code "70") (name "Net-(C64-PadP$1)") (class "Default")
      (node (ref "C64") (pin "P$1") (pinfunction "P$1_P$1") (pintype "passive"))
      (node (ref "R11") (pin "P$2") (pinfunction "P$2_P$2") (pintype "passive"))
    )
    (net (code "71") (name "Net-(C65-PadP$2)") (class "Default")
      (node (ref "C65") (pin "P$2") (pinfunction "P$2_P$2") (pintype "passive"))
      (node (ref "R12") (pin "P$1") (pinfunction "P$1_P$1") (pintype "passive"))
    )
    (net (code "72") (name "Net-(C66-PadP$1)") (class "Default")
      (node (ref "C66") (pin "P$1") (pinfunction "P$1_P$1") (pintype "passive"))
      (node (ref "R18") (pin "P$2") (pinfunction "P$2_P$2") (pintype "passive"))
    )
    (net (code "73") (name "Net-(C67-PadP$2)") (class "Default")
      (node (ref "C67") (pin "P$2") (pinfunction "P$2_P$2") (pintype "passive"))
      (node (ref "R19") (pin "P$1") (pinfunction "P$1_P$1") (pintype "passive"))
    )
    (net (code "74") (name "Net-(C68-PadP$1)") (class "Default")
      (node (ref "C68") (pin "P$1") (pinfunction "P$1_P$1") (pintype "passive"))
      (node (ref "R20") (pin "P$2") (pinfunction "P$2_P$2") (pintype "passive"))
    )
    (net (code "75") (name "Net-(C69-PadP$2)") (class "Default")
      (node (ref "C69") (pin "P$2") (pinfunction "P$2_P$2") (pintype "passive"))
      (node (ref "R21") (pin "P$1") (pinfunction "P$1_P$1") (pintype "passive"))
    )
    (net (code "76") (name "Net-(D2-PadANODE)") (class "Default")
      (node (ref "D2") (pin "ANODE") (pinfunction "ANODE_ANODE") (pintype "power_in"))
      (node (ref "R2") (pin "P$2") (pinfunction "P$2_P$2") (pintype "passive"))
    )
    (net (code "77") (name "Net-(D3-PadANODE)") (class "Default")
      (node (ref "D3") (pin "ANODE") (pinfunction "ANODE_ANODE") (pintype "power_in"))
      (node (ref "R1") (pin "P$2") (pinfunction "P$2_P$2") (pintype "passive"))
    )
    (net (code "78") (name "Net-(U4-VCC)") (class "Default")
      (node (ref "C20") (pin "P$1") (pinfunction "P$1_P$1") (pintype "passive"))
      (node (ref "U4") (pin "3") (pinfunction "VCC_3") (pintype "power_in"))
    )
    (net (code "79") (name "Net-(U5-CPH)") (class "Default")
      (node (ref "C16") (pin "P$1") (pinfunction "P$1_P$1") (pintype "passive"))
      (node (ref "U5") (pin "2") (pinfunction "CPH_2") (pintype "bidirectional"))
    )
    (net (code "80") (name "Net-(U5-CPL)") (class "Default")
      (node (ref "C16") (pin "P$2") (pinfunction "P$2_P$2") (pintype "passive"))
      (node (ref "U5") (pin "1") (pinfunction "CPL_1") (pintype "bidirectional"))
    )
    (net (code "81") (name "Net-(U5-DVDD)") (class "Default")
      (node (ref "C17") (pin "P$2") (pinfunction "P$2_P$2") (pintype "passive"))
      (node (ref "U5") (pin "38") (pinfunction "DVDD_38") (pintype "bidirectional"))
    )
    (net (code "82") (name "Net-(U5-VCP)") (class "Default")
      (node (ref "C15") (pin "P$2") (pinfunction "P$2_P$2") (pintype "passive"))
      (node (ref "U5") (pin "5") (pinfunction "VCP_5") (pintype "bidirectional"))
    )
    (net (code "83") (name "Net-(U5-VGLS)") (class "Default")
      (node (ref "C38") (pin "P$2") (pinfunction "P$2_P$2") (pintype "passive"))
      (node (ref "U5") (pin "40") (pinfunction "VGLS_40") (pintype "bidirectional"))
    )
    (net (code "84") (name "V+") (class "Default")
      (node (ref "C14") (pin "P$1") (pinfunction "P$1_P$1") (pintype "passive"))
      (node (ref "C15") (pin "P$1") (pinfunction "P$1_P$1") (pintype "passive"))
      (node (ref "C19") (pin "P$1") (pinfunction "P$1_P$1") (pintype "passive"))
      (node (ref "C22") (pin "P$1") (pinfunction "P$1_P$1") (pintype "passive"))
      (node (ref "C23") (pin "P$1") (pinfunction "P$1_P$1") (pintype "passive"))
      (node (ref "C24") (pin "P$1") (pinfunction "P$1_P$1") (pintype "passive"))
      (node (ref "C25") (pin "P$1") (pinfunction "P$1_P$1") (pintype "passive"))
      (node (ref "C26") (pin "P$1") (pinfunction "P$1_P$1") (pintype "passive"))
      (node (ref "C27") (pin "P$1") (pinfunction "P$1_P$1") (pintype "passive"))
      (node (ref "C28") (pin "P$1") (pinfunction "P$1_P$1") (pintype "passive"))
      (node (ref "C29") (pin "P$1") (pinfunction "P$1_P$1") (pintype "passive"))
      (node (ref "C30") (pin "P$1") (pinfunction "P$1_P$1") (pintype "passive"))
      (node (ref "C31") (pin "P$1") (pinfunction "P$1_P$1") (pintype "passive"))
      (node (ref "C32") (pin "P$1") (pinfunction "P$1_P$1") (pintype "passive"))
      (node (ref "C33") (pin "P$1") (pinfunction "P$1_P$1") (pintype "passive"))
      (node (ref "C34") (pin "P$1") (pinfunction "P$1_P$1") (pintype "passive"))
      (node (ref "C35") (pin "P$1") (pinfunction "P$1_P$1") (pintype "passive"))
      (node (ref "C36") (pin "P$1") (pinfunction "P$1_P$1") (pintype "passive"))
      (node (ref "C37") (pin "P$1") (pinfunction "P$1_P$1") (pintype "passive"))
      (node (ref "C39") (pin "P$1") (pinfunction "P$1_P$1") (pintype "passive"))
      (node (ref "C40") (pin "P$1") (pinfunction "P$1_P$1") (pintype "passive"))
      (node (ref "C41") (pin "P$1") (pinfunction "P$1_P$1") (pintype "passive"))
      (node (ref "C42") (pin "P$1") (pinfunction "P$1_P$1") (pintype "passive"))
      (node (ref "C43") (pin "P$1") (pinfunction "P$1_P$1") (pintype "passive"))
      (node (ref "C44") (pin "P$1") (pinfunction "P$1_P$1") (pintype "passive"))
      (node (ref "C45") (pin "P$1") (pinfunction "P$1_P$1") (pintype "passive"))
      (node (ref "C46") (pin "P$1") (pinfunction "P$1_P$1") (pintype "passive"))
      (node (ref "C47") (pin "P$1") (pinfunction "P$1_P$1") (pintype "passive"))
      (node (ref "C48") (pin "P$1") (pinfunction "P$1_P$1") (pintype "passive"))
      (node (ref "C49") (pin "P$1") (pinfunction "P$1_P$1") (pintype "passive"))
      (node (ref "C50") (pin "P$1") (pinfunction "P$1_P$1") (pintype "passive"))
      (node (ref "C51") (pin "P$1") (pinfunction "P$1_P$1") (pintype "passive"))
      (node (ref "C52") (pin "P$1") (pinfunction "P$1_P$1") (pintype "passive"))
      (node (ref "C53") (pin "P$1") (pinfunction "P$1_P$1") (pintype "passive"))
      (node (ref "C54") (pin "P$1") (pinfunction "P$1_P$1") (pintype "passive"))
      (node (ref "C61") (pin "P$1") (pinfunction "P$1_P$1") (pintype "passive"))
      (node (ref "C62") (pin "P$1") (pinfunction "P$1_P$1") (pintype "passive"))
      (node (ref "C63") (pin "P$1") (pinfunction "P$1_P$1") (pintype "passive"))
      (node (ref "J1") (pin "1") (pinfunction "1_1") (pintype "passive"))
      (node (ref "J2") (pin "1") (pinfunction "1_1") (pintype "passive"))
      (node (ref "Q1") (pin "5") (pinfunction "D_5") (pintype "passive"))
      (node (ref "Q1") (pin "6") (pinfunction "D_6") (pintype "passive"))
      (node (ref "Q1") (pin "7") (pinfunction "D_7") (pintype "passive"))
      (node (ref "Q1") (pin "8") (pinfunction "D_8") (pintype "passive"))
      (node (ref "Q1") (pin "PAD") (pinfunction "D_PAD") (pintype "passive"))
      (node (ref "Q3") (pin "5") (pinfunction "D_5") (pintype "passive"))
      (node (ref "Q3") (pin "6") (pinfunction "D_6") (pintype "passive"))
      (node (ref "Q3") (pin "7") (pinfunction "D_7") (pintype "passive"))
      (node (ref "Q3") (pin "8") (pinfunction "D_8") (pintype "passive"))
      (node (ref "Q3") (pin "PAD") (pinfunction "D_PAD") (pintype "passive"))
      (node (ref "Q5") (pin "5") (pinfunction "D_5") (pintype "passive"))
      (node (ref "Q5") (pin "6") (pinfunction "D_6") (pintype "passive"))
      (node (ref "Q5") (pin "7") (pinfunction "D_7") (pintype "passive"))
      (node (ref "Q5") (pin "8") (pinfunction "D_8") (pintype "passive"))
      (node (ref "Q5") (pin "PAD") (pinfunction "D_PAD") (pintype "passive"))
      (node (ref "R11") (pin "P$1") (pinfunction "P$1_P$1") (pintype "passive"))
      (node (ref "R18") (pin "P$1") (pinfunction "P$1_P$1") (pintype "passive"))
      (node (ref "R20") (pin "P$1") (pinfunction "P$1_P$1") (pintype "passive"))
      (node (ref "R5") (pin "P$2") (pinfunction "P$2_P$2") (pintype "passive"))
      (node (ref "U4") (pin "1") (pinfunction "VIN_1") (pintype "input"))
      (node (ref "U4") (pin "2") (pinfunction "EN/UVLO_2") (pintype "input"))
      (node (ref "U5") (pin "3") (pinfunction "VM_3") (pintype "bidirectional"))
      (node (ref "U5") (pin "4") (pinfunction "VDRAIN_4") (pintype "bidirectional"))
    )
    (net (code "85") (name "V-") (class "Default")
      (node (ref "C14") (pin "P$2") (pinfunction "P$2_P$2") (pintype "passive"))
      (node (ref "C17") (pin "P$1") (pinfunction "P$1_P$1") (pintype "passive"))
      (node (ref "C19") (pin "P$2") (pinfunction "P$2_P$2") (pintype "passive"))
      (node (ref "C22") (pin "P$2") (pinfunction "P$2_P$2") (pintype "passive"))
      (node (ref "C23") (pin "P$2") (pinfunction "P$2_P$2") (pintype "passive"))
      (node (ref "C24") (pin "P$2") (pinfunction "P$2_P$2") (pintype "passive"))
      (node (ref "C25") (pin "P$2") (pinfunction "P$2_P$2") (pintype "passive"))
      (node (ref "C26") (pin "P$2") (pinfunction "P$2_P$2") (pintype "passive"))
      (node (ref "C27") (pin "P$2") (pinfunction "P$2_P$2") (pintype "passive"))
      (node (ref "C28") (pin "P$2") (pinfunction "P$2_P$2") (pintype "passive"))
      (node (ref "C29") (pin "P$2") (pinfunction "P$2_P$2") (pintype "passive"))
      (node (ref "C30") (pin "P$2") (pinfunction "P$2_P$2") (pintype "passive"))
      (node (ref "C31") (pin "P$2") (pinfunction "P$2_P$2") (pintype "passive"))
      (node (ref "C32") (pin "P$2") (pinfunction "P$2_P$2") (pintype "passive"))
      (node (ref "C33") (pin "P$2") (pinfunction "P$2_P$2") (pintype "passive"))
      (node (ref "C34") (pin "P$2") (pinfunction "P$2_P$2") (pintype "passive"))
      (node (ref "C35") (pin "P$2") (pinfunction "P$2_P$2") (pintype "passive"))
      (node (ref "C36") (pin "P$2") (pinfunction "P$2_P$2") (pintype "passive"))
      (node (ref "C37") (pin "P$2") (pinfunction "P$2_P$2") (pintype "passive"))
      (node (ref "C38") (pin "P$1") (pinfunction "P$1_P$1") (pintype "passive"))
      (node (ref "C39") (pin "P$2") (pinfunction "P$2_P$2") (pintype "passive"))
      (node (ref "C40") (pin "P$2") (pinfunction "P$2_P$2") (pintype "passive"))
      (node (ref "C41") (pin "P$2") (pinfunction "P$2_P$2") (pintype "passive"))
      (node (ref "C42") (pin "P$2") (pinfunction "P$2_P$2") (pintype "passive"))
      (node (ref "C43") (pin "P$2") (pinfunction "P$2_P$2") (pintype "passive"))
      (node (ref "C44") (pin "P$2") (pinfunction "P$2_P$2") (pintype "passive"))
      (node (ref "C45") (pin "P$2") (pinfunction "P$2_P$2") (pintype "passive"))
      (node (ref "C46") (pin "P$2") (pinfunction "P$2_P$2") (pintype "passive"))
      (node (ref "C47") (pin "P$2") (pinfunction "P$2_P$2") (pintype "passive"))
      (node (ref "C48") (pin "P$2") (pinfunction "P$2_P$2") (pintype "passive"))
      (node (ref "C49") (pin "P$2") (pinfunction "P$2_P$2") (pintype "passive"))
      (node (ref "C50") (pin "P$2") (pinfunction "P$2_P$2") (pintype "passive"))
      (node (ref "C51") (pin "P$2") (pinfunction "P$2_P$2") (pintype "passive"))
      (node (ref "C52") (pin "P$2") (pinfunction "P$2_P$2") (pintype "passive"))
      (node (ref "C53") (pin "P$2") (pinfunction "P$2_P$2") (pintype "passive"))
      (node (ref "C54") (pin "P$2") (pinfunction "P$2_P$2") (pintype "passive"))
      (node (ref "C55") (pin "P$2") (pinfunction "P$2_P$2") (pintype "passive"))
      (node (ref "D1") (pin "2") (pinfunction "A_2") (pintype "bidirectional"))
      (node (ref "D5") (pin "2") (pinfunction "A_2") (pintype "bidirectional"))
      (node (ref "D6") (pin "2") (pinfunction "A_2") (pintype "bidirectional"))
      (node (ref "J1") (pin "2") (pinfunction "2_2") (pintype "passive"))
      (node (ref "J2") (pin "2") (pinfunction "2_2") (pintype "passive"))
      (node (ref "R10") (pin "P$2") (pinfunction "P$2_P$2") (pintype "passive"))
      (node (ref "RA") (pin "1") (pinfunction "1_1") (pintype "passive"))
      (node (ref "RB") (pin "1") (pinfunction "1_1") (pintype "passive"))
      (node (ref "RC") (pin "1") (pinfunction "1_1") (pintype "passive"))
      (node (ref "SH1") (pin "2") (pinfunction "P$2_2") (pintype "bidirectional"))
      (node (ref "SH2") (pin "2") (pinfunction "P$2_2") (pintype "bidirectional"))
      (node (ref "SH3") (pin "2") (pinfunction "P$2_2") (pintype "bidirectional"))
      (node (ref "SH4") (pin "1") (pinfunction "P$1_1") (pintype "bidirectional"))
      (node (ref "U5") (pin "39") (pinfunction "GND_39") (pintype "bidirectional"))
      (node (ref "U5") (pin "P1") (pinfunction "PAD_P1") (pintype "bidirectional"))
      (node (ref "U5") (pin "P12") (pinfunction "PAD_P12") (pintype "bidirectional"))
      (node (ref "U5") (pin "P13") (pinfunction "PAD_P13") (pintype "bidirectional"))
      (node (ref "U5") (pin "P14") (pinfunction "PAD_P14") (pintype "bidirectional"))
      (node (ref "U5") (pin "P17") (pinfunction "PAD_P17") (pintype "bidirectional"))
      (node (ref "U5") (pin "P18") (pinfunction "PAD_P18") (pintype "bidirectional"))
      (node (ref "U5") (pin "P19") (pinfunction "PAD_P19") (pintype "bidirectional"))
      (node (ref "U5") (pin "P2") (pinfunction "PAD_P2") (pintype "bidirectional"))
      (node (ref "U5") (pin "P3") (pinfunction "PAD_P3") (pintype "bidirectional"))
      (node (ref "U5") (pin "P7") (pinfunction "PAD_P7") (pintype "bidirectional"))
      (node (ref "U5") (pin "P8") (pinfunction "PAD_P8") (pintype "bidirectional"))
      (node (ref "U5") (pin "P9") (pinfunction "PAD_P9") (pintype "bidirectional"))
      (node (ref "U5") (pin "PAD") (pinfunction "PAD_PAD") (pintype "bidirectional"))
    )
    (net (code "86") (name "unconnected-(M1-PadP$1)") (class "Default")
      (node (ref "M1") (pin "P$1") (pinfunction "P$1_P$1") (pintype "bidirectional"))
    )
    (net (code "87") (name "unconnected-(M2-PadP$1)") (class "Default")
      (node (ref "M2") (pin "P$1") (pinfunction "P$1_P$1") (pintype "bidirectional"))
    )
    (net (code "88") (name "unconnected-(M4-PadP$1)") (class "Default")
      (node (ref "M4") (pin "P$1") (pinfunction "P$1_P$1") (pintype "bidirectional"))
    )
    (net (code "89") (name "unconnected-(SWD-Pad1)") (class "Default")
      (node (ref "SWD") (pin "1") (pinfunction "1_1") (pintype "passive"))
    )
    (net (code "90") (name "unconnected-(U1-PA15-Pad38)") (class "Default")
      (node (ref "U1") (pin "38") (pinfunction "PA15_38") (pintype "bidirectional"))
    )
    (net (code "91") (name "unconnected-(U1-PB3-Pad41)") (class "Default")
      (node (ref "U1") (pin "41") (pinfunction "PB3_41") (pintype "bidirectional"))
    )
    (net (code "92") (name "unconnected-(U1-PB10-Pad22)") (class "Default")
      (node (ref "U1") (pin "22") (pinfunction "PB10_22") (pintype "bidirectional"))
    )
    (net (code "93") (name "unconnected-(U1-PC6-Pad29)") (class "Default")
      (node (ref "U1") (pin "29") (pinfunction "PC6_29") (pintype "bidirectional"))
    )
    (net (code "94") (name "unconnected-(U3-I-Pad14)") (class "Default")
      (node (ref "U3") (pin "14") (pinfunction "I_14") (pintype "bidirectional"))
    )
    (net (code "95") (name "unconnected-(U3-PWM-Pad8)") (class "Default")
      (node (ref "U3") (pin "8") (pinfunction "PWM_8") (pintype "bidirectional"))
    )
    (net (code "96") (name "unconnected-(U3-VDD5V-Pad11)") (class "Default")
      (node (ref "U3") (pin "11") (pinfunction "VDD5V_11") (pintype "bidirectional"))
    )
    (net (code "97") (name "unconnected-(U4-MODE-Pad5)") (class "Default")
      (node (ref "U4") (pin "5") (pinfunction "MODE_5") (pintype "input"))
    )
    (net (code "98") (name "unconnected-(U4-~{RESET}-Pad6)") (class "Default")
      (node (ref "U4") (pin "6") (pinfunction "~{RESET}_6") (pintype "output"))
    )
  )
)
